# ProPrj_M-power_2025-07-25.net
KiCad netlist of a schematic drawn in EasyEDA Pro
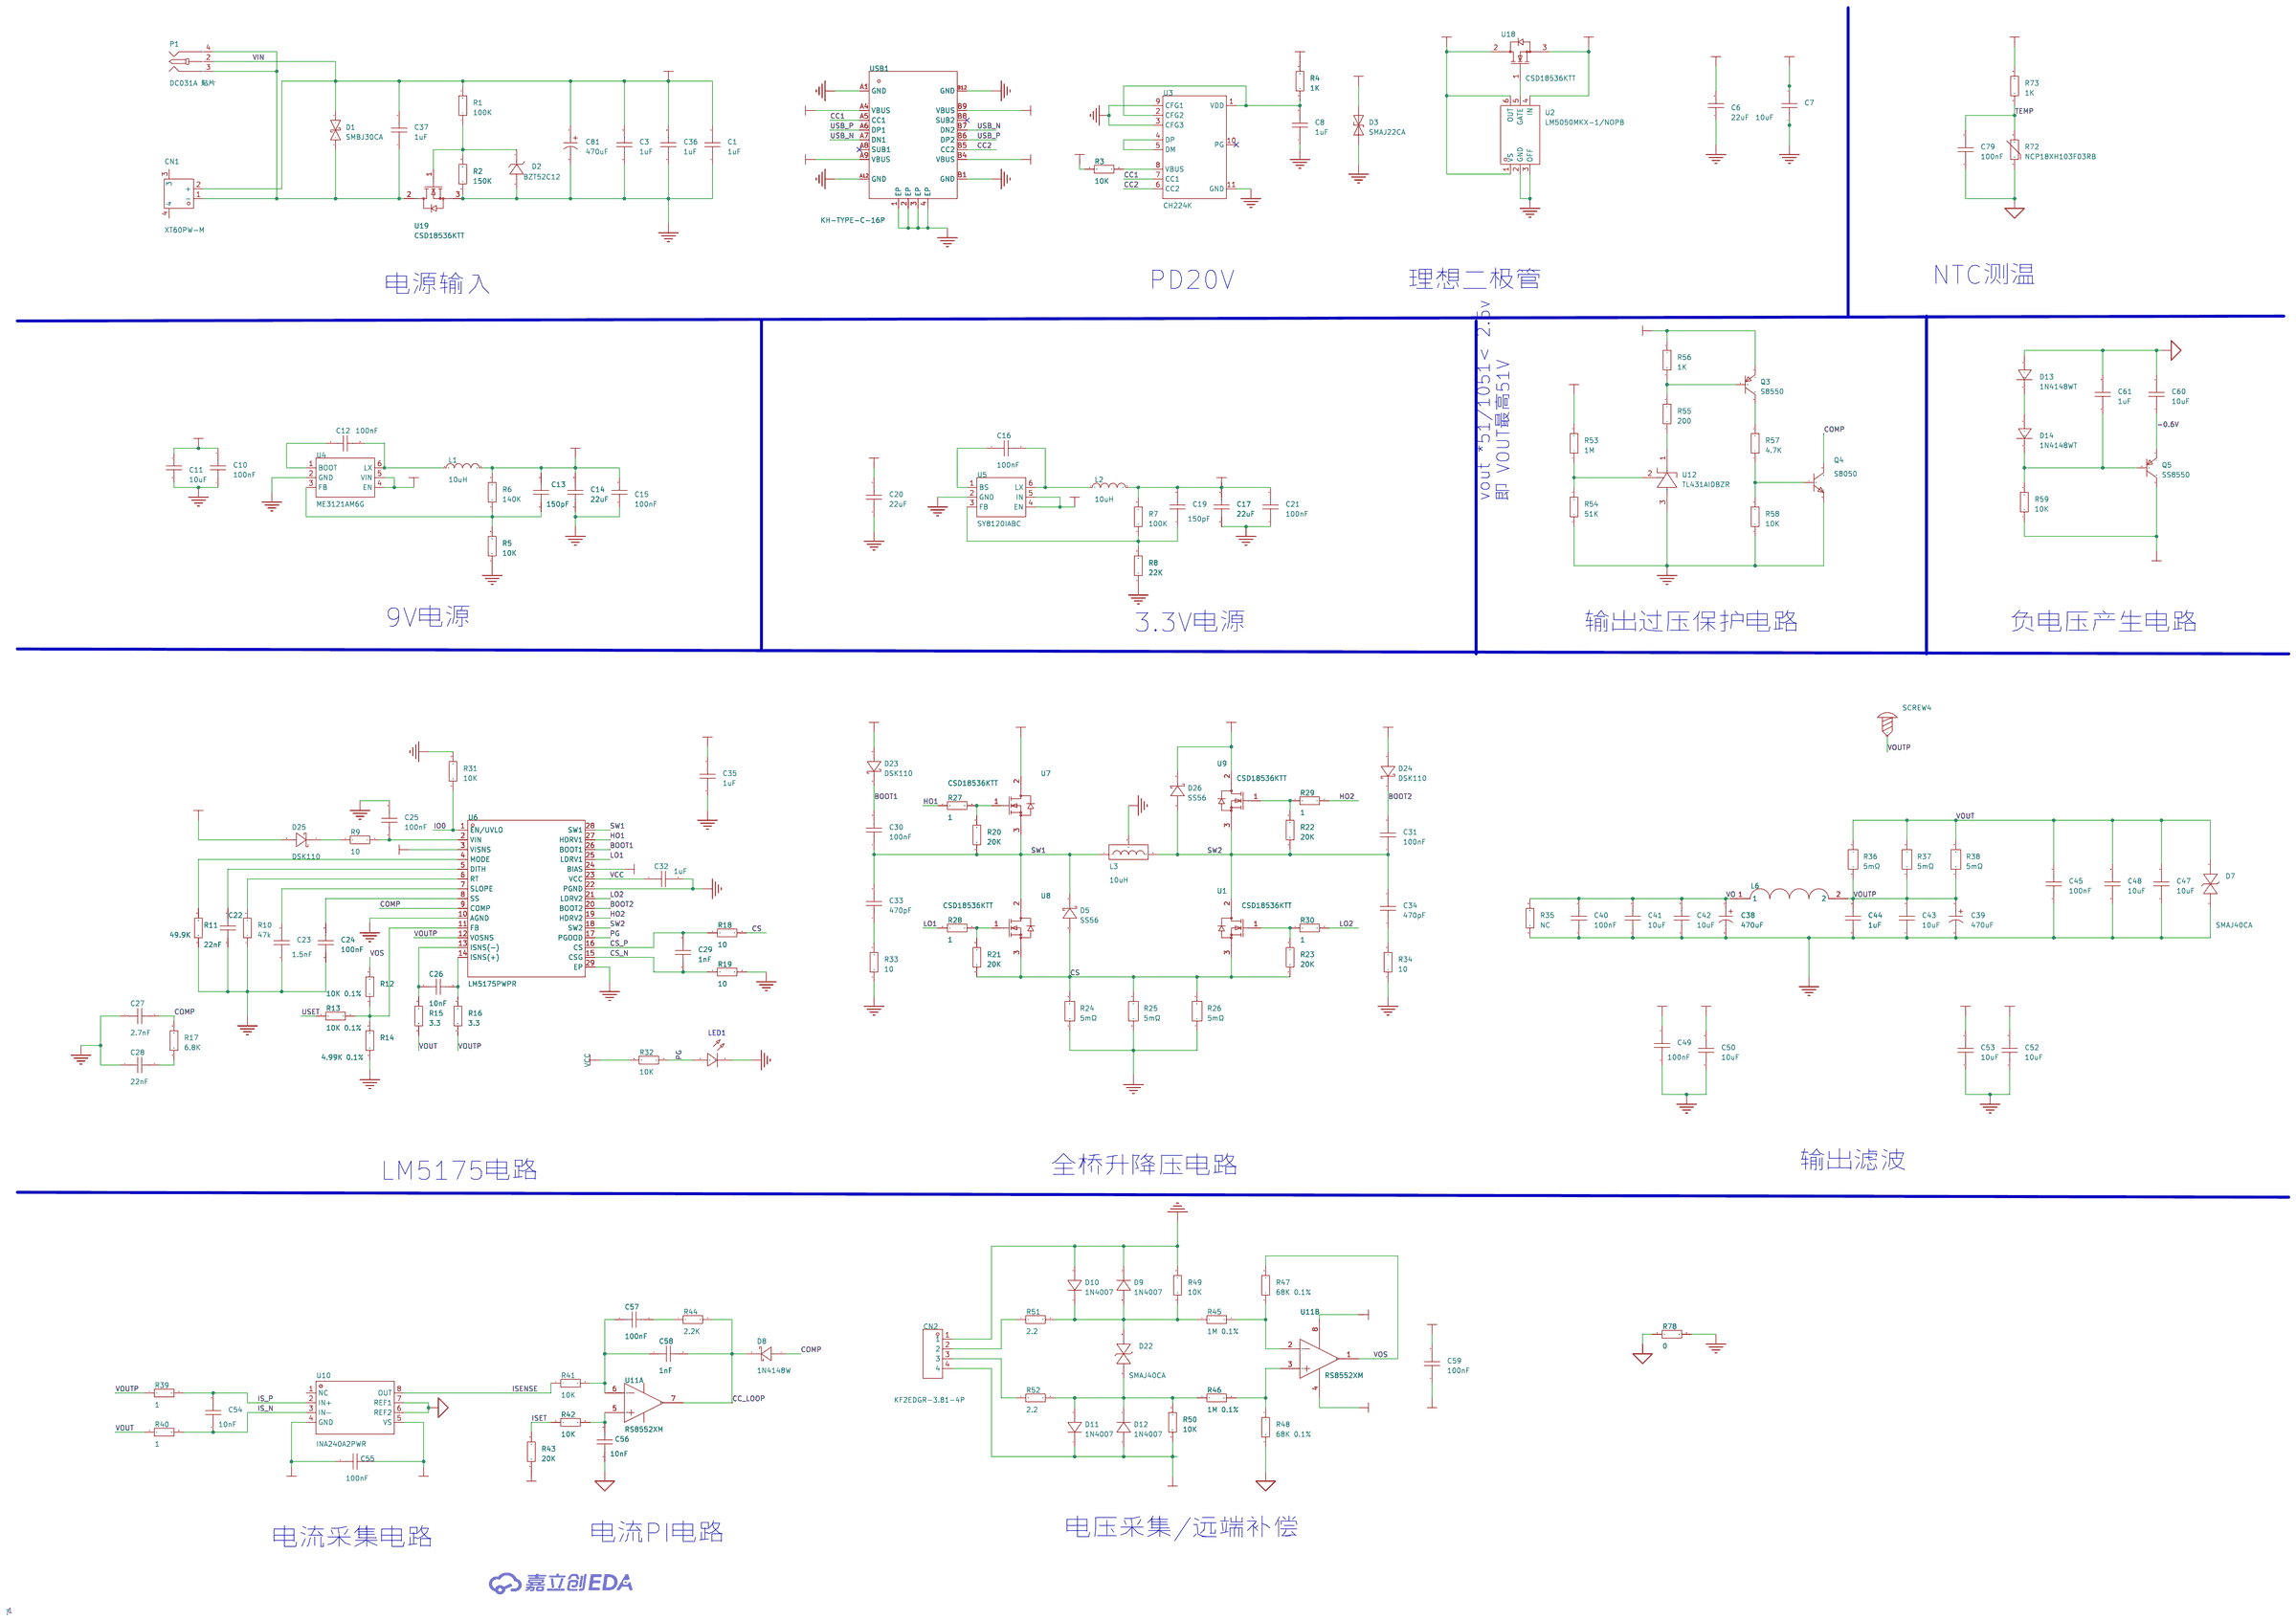
[diagram p0: 功率]
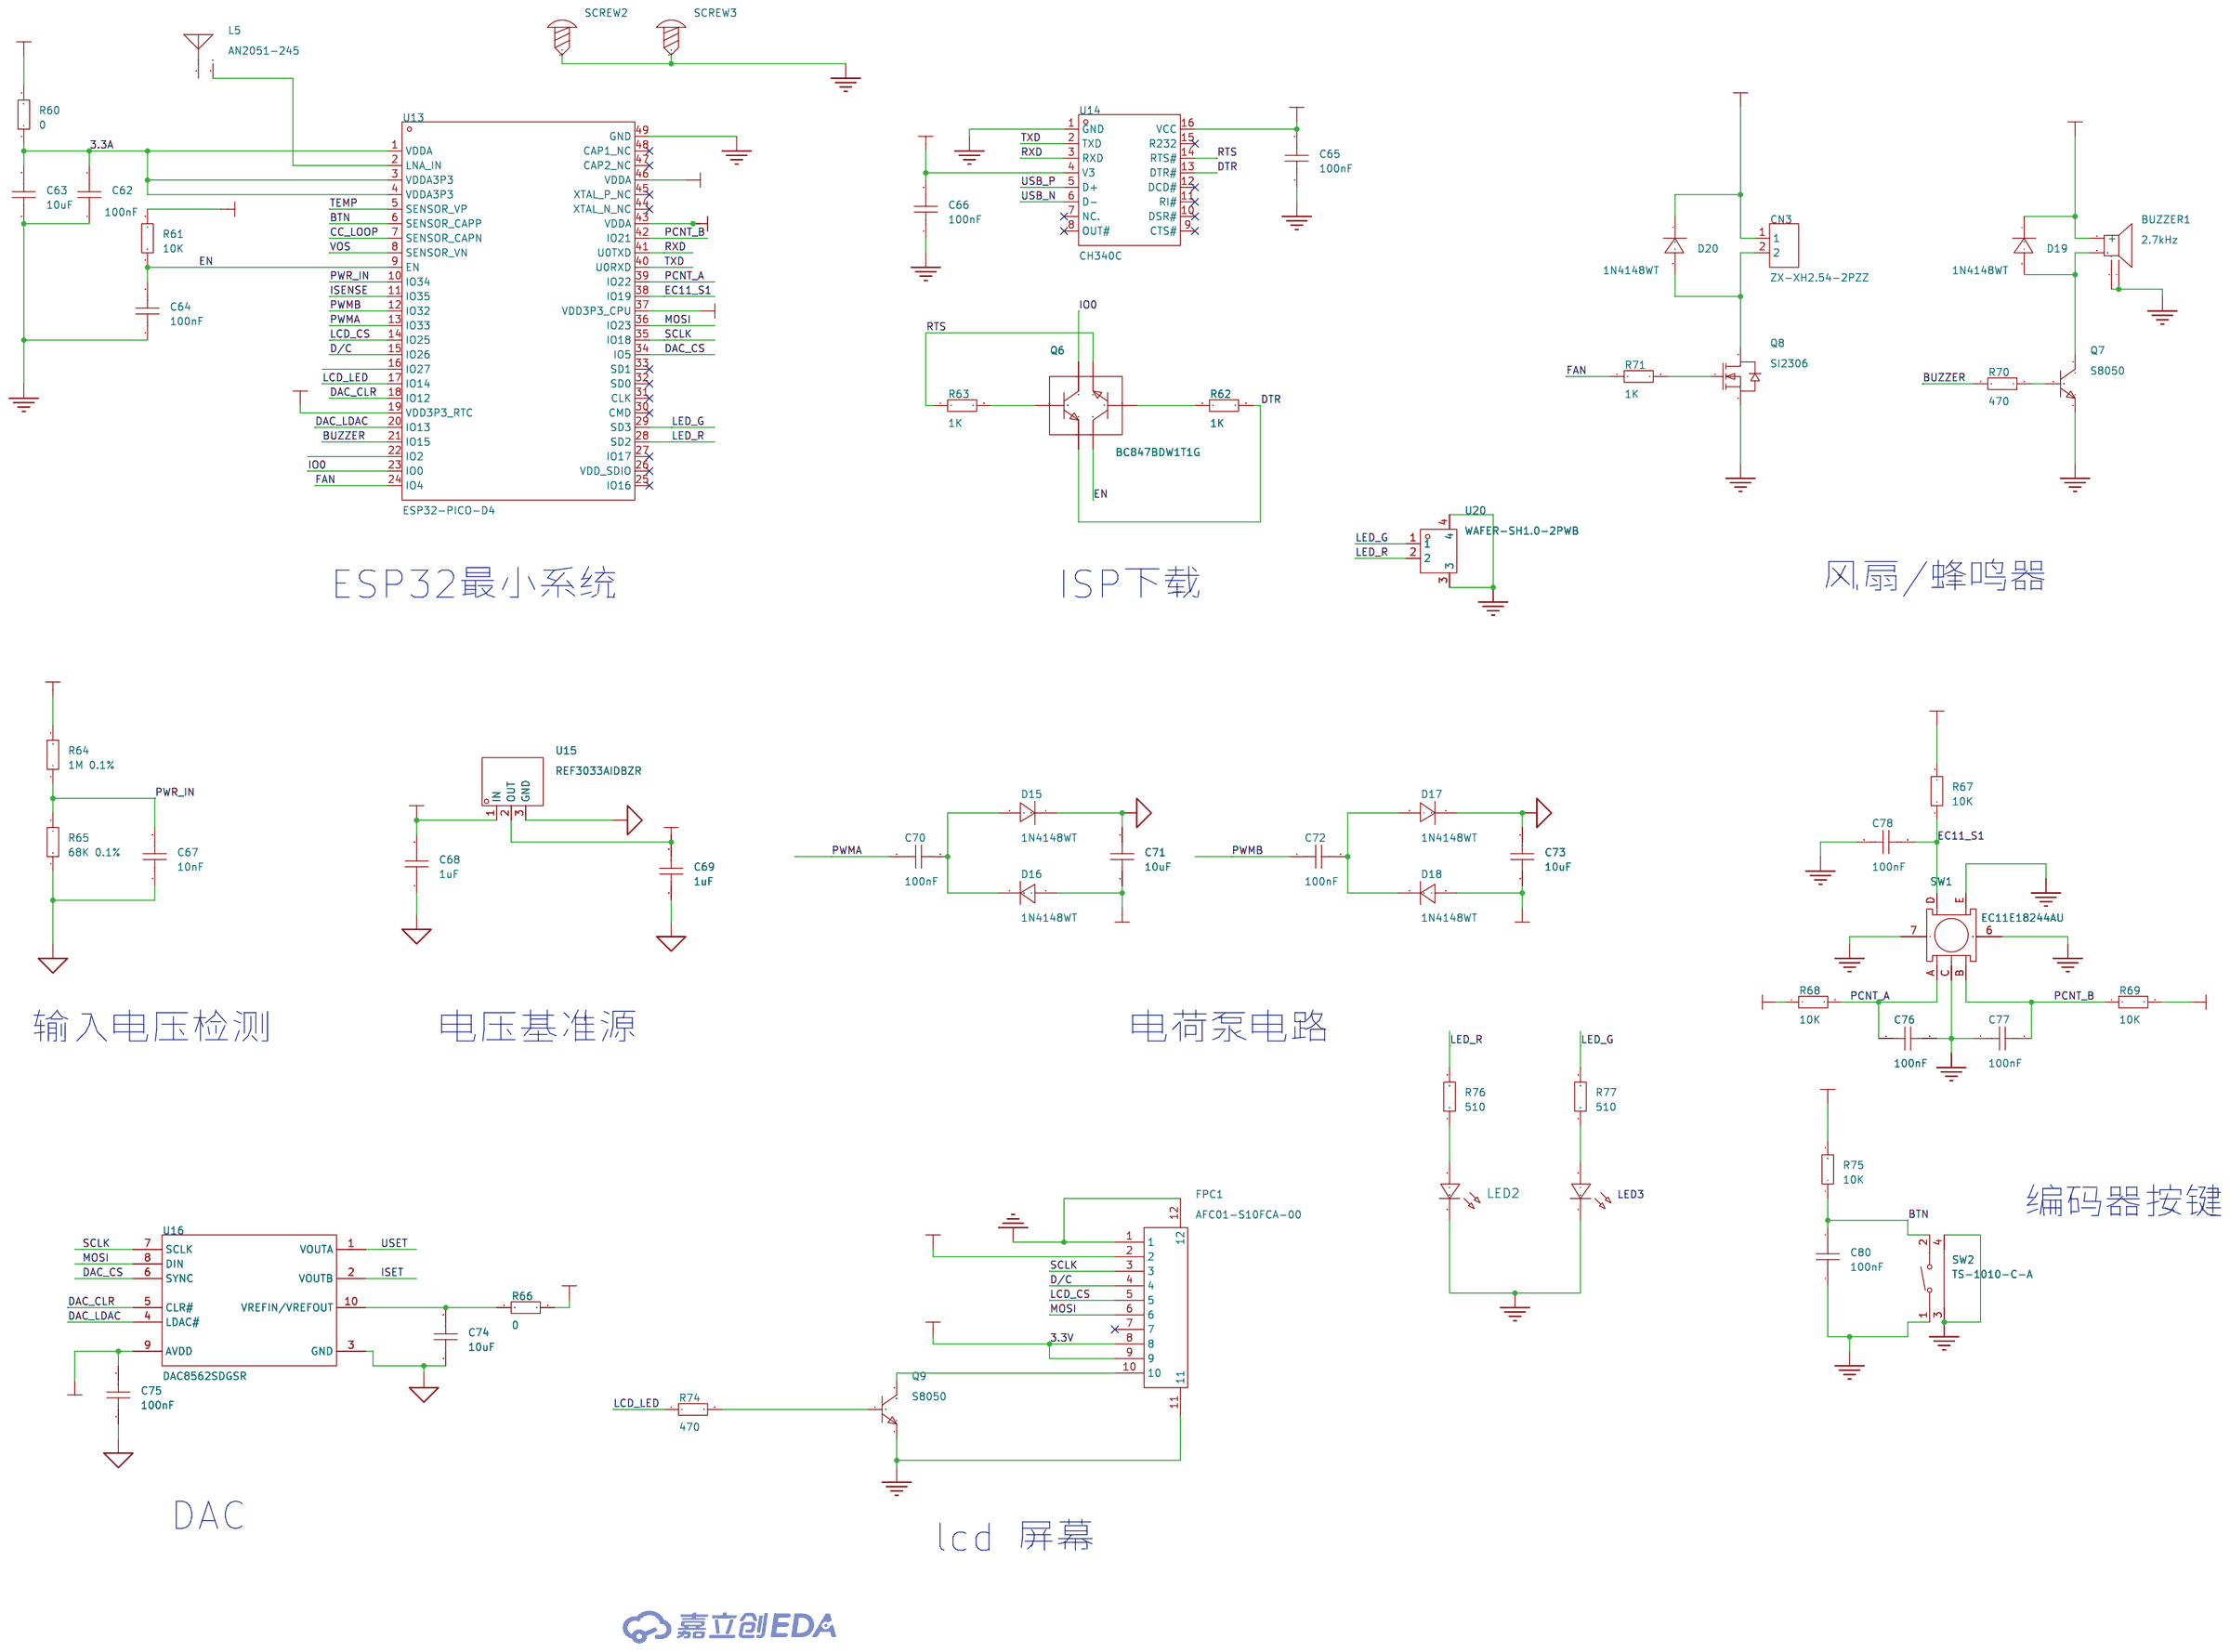
[diagram p1: 控制]

(export (version "E")
  (design (tool "Eeschema 10.0.6"))
  (components
    (comp (ref "C1")
      (value "1uF")
      (footprint "easyedapro:C0603")
      (fields
        (field (name "Manufacturer Part") "CL31B105KBHNNNE")
        (field (name "Manufacturer") "SAMSUNG(三星)")
      )
      (libsource (lib "easyedapro") (part "CapAcitance"))
    )
    (comp (ref "C3")
      (value "1uF")
      (footprint "easyedapro:C0603")
      (fields
        (field (name "Manufacturer Part") "CL31B105KBHNNNE")
        (field (name "Manufacturer") "SAMSUNG(三星)")
      )
      (libsource (lib "easyedapro") (part "CapAcitance"))
    )
    (comp (ref "C6")
      (value "22uF")
      (footprint "easyedapro:C1206")
      (description "容值:22uF;精度:±10%;额定电压:25V;材质(温度系数):X5R;")
      (fields
        (field (name "Manufacturer Part") "CL31A226KAHNNNE")
        (field (name "Manufacturer") "SAMSUNG(三星)")
      )
      (libsource (lib "easyedapro") (part "CL31A226KAHNNNE"))
    )
    (comp (ref "C7")
      (value "10uF")
      (footprint "easyedapro:C0603")
      (description "容值:10uF;精度:±20%;额定电压:25V;材质(温度系数):X5R;")
      (fields
        (field (name "Manufacturer Part") "CL10A106MA8NRNC")
        (field (name "Manufacturer") "SAMSUNG(三星)")
      )
      (libsource (lib "easyedapro") (part "CL10A106MA8NRNC"))
    )
    (comp (ref "C8")
      (value "1uF")
      (footprint "easyedapro:C0603")
      (libsource (lib "easyedapro") (part "CapAcitance"))
    )
    (comp (ref "C10")
      (value "100nF")
      (footprint "easyedapro:C0603")
      (libsource (lib "easyedapro") (part "CapAcitance"))
    )
    (comp (ref "C11")
      (value "10uF")
      (footprint "easyedapro:C1206")
      (description "容值:10uF;精度:±10%;额定电压:50V;材质(温度系数):X5R;")
      (fields
        (field (name "Manufacturer Part") "CL31A106KBHNNNE")
        (field (name "Manufacturer") "SAMSUNG(三星)")
      )
      (libsource (lib "easyedapro") (part "CL31A106KBHNNNE"))
    )
    (comp (ref "C12")
      (value "100nF")
      (footprint "easyedapro:C0603")
      (libsource (lib "easyedapro") (part "CapAcitance"))
    )
    (comp (ref "C13")
      (value "150pF")
      (footprint "easyedapro:C0603")
      (libsource (lib "easyedapro") (part "CapAcitance"))
    )
    (comp (ref "C14")
      (value "22uF")
      (footprint "easyedapro:C0805")
      (description "容值:22uF;精度:±20%;额定电压:25V;材质(温度系数):X5R;")
      (fields
        (field (name "Manufacturer Part") "CL21A226MAYNNNE")
        (field (name "Manufacturer") "SAMSUNG(三星)")
      )
      (libsource (lib "easyedapro") (part "CL21A226MAYNNNE"))
    )
    (comp (ref "C15")
      (value "100nF")
      (footprint "easyedapro:C1206")
      (description "容值:100uF;精度:±20%;额定电压:6.3V;材质(温度系数):X5R;")
      (fields
        (field (name "Manufacturer Part") "CL31A107MQHNNNE")
        (field (name "Manufacturer") "SAMSUNG(三星)")
      )
      (libsource (lib "easyedapro") (part "CL31A107MQHNNNE"))
    )
    (comp (ref "C16")
      (value "100nF")
      (footprint "easyedapro:C0603")
      (libsource (lib "easyedapro") (part "CapAcitance"))
    )
    (comp (ref "C17")
      (value "22uF")
      (footprint "easyedapro:C0603")
      (description "容值:22uF;精度:±20%;额定电压:6.3V;材质(温度系数):X5R;")
      (fields
        (field (name "Manufacturer Part") "CL10A226MQ8NRNC")
        (field (name "Manufacturer") "SAMSUNG(三星)")
      )
      (libsource (lib "easyedapro") (part "CL10A226MQ8NRNC"))
    )
    (comp (ref "C19")
      (value "150pF")
      (footprint "easyedapro:C0603")
      (libsource (lib "easyedapro") (part "CapAcitance"))
    )
    (comp (ref "C20")
      (value "22uF")
      (footprint "easyedapro:C0603")
      (description "容值:22uF;精度:±20%;额定电压:6.3V;材质(温度系数):X5R;")
      (fields
        (field (name "Manufacturer Part") "CL10A226MQ8NRNC")
        (field (name "Manufacturer") "SAMSUNG(三星)")
      )
      (libsource (lib "easyedapro") (part "CL10A226MQ8NRNC"))
    )
    (comp (ref "C21")
      (value "100nF")
      (footprint "easyedapro:C0603")
      (libsource (lib "easyedapro") (part "CapAcitance"))
    )
    (comp (ref "C22")
      (value "22nF")
      (footprint "easyedapro:C0603")
      (libsource (lib "easyedapro") (part "CapAcitance"))
    )
    (comp (ref "C23")
      (value "1.5nF")
      (footprint "easyedapro:C0603")
      (libsource (lib "easyedapro") (part "CapAcitance"))
    )
    (comp (ref "C24")
      (value "100nF")
      (footprint "easyedapro:C0603")
      (libsource (lib "easyedapro") (part "CapAcitance"))
    )
    (comp (ref "C25")
      (value "100nF")
      (footprint "easyedapro:C0603")
      (libsource (lib "easyedapro") (part "CapAcitance"))
    )
    (comp (ref "C26")
      (value "10nF")
      (footprint "easyedapro:C0603")
      (libsource (lib "easyedapro") (part "CapAcitance"))
    )
    (comp (ref "C27")
      (value "2.7nF")
      (footprint "easyedapro:C0603")
      (libsource (lib "easyedapro") (part "CapAcitance"))
    )
    (comp (ref "C28")
      (value "22nF")
      (footprint "easyedapro:C0603")
      (libsource (lib "easyedapro") (part "CapAcitance"))
    )
    (comp (ref "C29")
      (value "1nF")
      (footprint "easyedapro:C0603")
      (libsource (lib "easyedapro") (part "CapAcitance"))
    )
    (comp (ref "C30")
      (value "100nF")
      (footprint "easyedapro:C0603")
      (libsource (lib "easyedapro") (part "CapAcitance"))
    )
    (comp (ref "C31")
      (value "100nF")
      (footprint "easyedapro:C0603")
      (libsource (lib "easyedapro") (part "CapAcitance"))
    )
    (comp (ref "C32")
      (value "1uF")
      (footprint "easyedapro:C0603")
      (libsource (lib "easyedapro") (part "CapAcitance"))
    )
    (comp (ref "C33")
      (value "470pF")
      (footprint "easyedapro:C0603")
      (libsource (lib "easyedapro") (part "CapAcitance"))
    )
    (comp (ref "C34")
      (value "470pF")
      (footprint "easyedapro:C0603")
      (libsource (lib "easyedapro") (part "CapAcitance"))
    )
    (comp (ref "C35")
      (value "1uF")
      (footprint "easyedapro:C0603")
      (libsource (lib "easyedapro") (part "CapAcitance"))
    )
    (comp (ref "C36")
      (value "1uF")
      (footprint "easyedapro:C0603")
      (fields
        (field (name "Manufacturer Part") "CL31B105KBHNNNE")
        (field (name "Manufacturer") "SAMSUNG(三星)")
      )
      (libsource (lib "easyedapro") (part "CapAcitance"))
    )
    (comp (ref "C37")
      (value "1uF")
      (footprint "easyedapro:C0603")
      (fields
        (field (name "Manufacturer Part") "CL31B105KBHNNNE")
        (field (name "Manufacturer") "SAMSUNG(三星)")
      )
      (libsource (lib "easyedapro") (part "CapAcitance"))
    )
    (comp (ref "C38")
      (value "470uF")
      (footprint "easyedapro:CAP-TH_BD10.0-P5.00-D0.6-FD-A")
      (description "容值:470uF;精度:±20%;额定电压:50V;纹波电流:4.1A@100Hz;等效串联电阻(ESR):18mΩ@100kHz;类型:-;")
      (fields (field (name "Manufacturer Part") "PA50V470M10x17") (field (name "Manufacturer") "捷而瑞"))
      (libsource (lib "easyedapro") (part "PA50V470M10X17"))
    )
    (comp (ref "C39")
      (value "470uF")
      (footprint "easyedapro:CAP-TH_BD10.0-P5.00-D0.6-FD-A")
      (description "容值:470uF;精度:±20%;额定电压:50V;纹波电流:4.1A@100Hz;等效串联电阻(ESR):18mΩ@100kHz;类型:-;")
      (fields (field (name "Manufacturer Part") "PA50V470M10x17") (field (name "Manufacturer") "捷而瑞"))
      (libsource (lib "easyedapro") (part "PA50V470M10X17"))
    )
    (comp (ref "C40")
      (value "100nF")
      (footprint "easyedapro:C0603")
      (libsource (lib "easyedapro") (part "CapAcitance"))
    )
    (comp (ref "C41")
      (value "10uF")
      (footprint "easyedapro:C0603")
      (fields
        (field (name "Manufacturer Part") "CL31B105KBHNNNE")
        (field (name "Manufacturer") "SAMSUNG(三星)")
      )
      (libsource (lib "easyedapro") (part "CapAcitance"))
    )
    (comp (ref "C42")
      (value "10uF")
      (footprint "easyedapro:C0603")
      (fields
        (field (name "Manufacturer Part") "CL31B105KBHNNNE")
        (field (name "Manufacturer") "SAMSUNG(三星)")
      )
      (libsource (lib "easyedapro") (part "CapAcitance"))
    )
    (comp (ref "C43")
      (value "10uF")
      (footprint "easyedapro:C0603")
      (fields
        (field (name "Manufacturer Part") "CL31B105KBHNNNE")
        (field (name "Manufacturer") "SAMSUNG(三星)")
      )
      (libsource (lib "easyedapro") (part "CapAcitance"))
    )
    (comp (ref "C44")
      (value "1uF")
      (footprint "easyedapro:C0603")
      (fields
        (field (name "Manufacturer Part") "CL31B105KBHNNNE")
        (field (name "Manufacturer") "SAMSUNG(三星)")
      )
      (libsource (lib "easyedapro") (part "CapAcitance"))
    )
    (comp (ref "C45")
      (value "100nF")
      (footprint "easyedapro:C0603")
      (libsource (lib "easyedapro") (part "CapAcitance"))
    )
    (comp (ref "C47")
      (value "10uF")
      (footprint "easyedapro:C0603")
      (fields
        (field (name "Manufacturer Part") "CL31B105KBHNNNE")
        (field (name "Manufacturer") "SAMSUNG(三星)")
      )
      (libsource (lib "easyedapro") (part "CapAcitance"))
    )
    (comp (ref "C48")
      (value "10uF")
      (footprint "easyedapro:C0603")
      (fields
        (field (name "Manufacturer Part") "CL31B105KBHNNNE")
        (field (name "Manufacturer") "SAMSUNG(三星)")
      )
      (libsource (lib "easyedapro") (part "CapAcitance"))
    )
    (comp (ref "C49")
      (value "100nF")
      (footprint "easyedapro:C0603")
      (libsource (lib "easyedapro") (part "CapAcitance"))
    )
    (comp (ref "C50")
      (value "10uF")
      (footprint "easyedapro:C0603")
      (fields
        (field (name "Manufacturer Part") "CL31B105KBHNNNE")
        (field (name "Manufacturer") "SAMSUNG(三星)")
      )
      (libsource (lib "easyedapro") (part "CapAcitance"))
    )
    (comp (ref "C52")
      (value "10uF")
      (footprint "easyedapro:C0603")
      (fields
        (field (name "Manufacturer Part") "CL31B105KBHNNNE")
        (field (name "Manufacturer") "SAMSUNG(三星)")
      )
      (libsource (lib "easyedapro") (part "CapAcitance"))
    )
    (comp (ref "C53")
      (value "10uF")
      (footprint "easyedapro:C0603")
      (fields
        (field (name "Manufacturer Part") "CL31B105KBHNNNE")
        (field (name "Manufacturer") "SAMSUNG(三星)")
      )
      (libsource (lib "easyedapro") (part "CapAcitance"))
    )
    (comp (ref "C54")
      (value "10nF")
      (footprint "easyedapro:C0603")
      (libsource (lib "easyedapro") (part "CapAcitance"))
    )
    (comp (ref "C55")
      (value "100nF")
      (footprint "easyedapro:C0603")
      (libsource (lib "easyedapro") (part "CapAcitance"))
    )
    (comp (ref "C56")
      (value "10nF")
      (footprint "easyedapro:C0603")
      (libsource (lib "easyedapro") (part "CapAcitance"))
    )
    (comp (ref "C57")
      (value "100nF")
      (footprint "easyedapro:C0603")
      (libsource (lib "easyedapro") (part "CapAcitance"))
    )
    (comp (ref "C58")
      (value "1nF")
      (footprint "easyedapro:C0603")
      (libsource (lib "easyedapro") (part "CapAcitance"))
    )
    (comp (ref "C59")
      (value "100nF")
      (footprint "easyedapro:C0603")
      (libsource (lib "easyedapro") (part "CapAcitance"))
    )
    (comp (ref "C60")
      (value "10uF")
      (footprint "easyedapro:C0603")
      (libsource (lib "easyedapro") (part "CapAcitance"))
    )
    (comp (ref "C61")
      (value "1uF")
      (footprint "easyedapro:C0603")
      (libsource (lib "easyedapro") (part "CapAcitance"))
    )
    (comp (ref "C79")
      (value "100nF")
      (footprint "easyedapro:C0603")
      (libsource (lib "easyedapro") (part "CapAcitance"))
    )
    (comp (ref "C81")
      (value "470uF")
      (footprint "easyedapro:CAP-TH_BD10.0-P5.00-D0.6-FD-A")
      (description "容值:470uF;精度:±20%;额定电压:50V;纹波电流:4.1A@100Hz;等效串联电阻(ESR):18mΩ@100kHz;类型:-;")
      (fields (field (name "Manufacturer Part") "PA50V470M10x17") (field (name "Manufacturer") "捷而瑞"))
      (libsource (lib "easyedapro") (part "PA50V470M10X17"))
    )
    (comp (ref "CN1")
      (value "XT60PW-M")
      (footprint "easyedapro:CONN-TH_XT60PW-M")
      (description "类别:-;类型1:-;")
      (fields (field (name "Manufacturer") "AMASS(艾迈斯)"))
      (libsource (lib "easyedapro") (part "XT60PW-M"))
    )
    (comp (ref "CN2")
      (value "KF2EDGR-3.81-4P")
      (footprint "easyedapro:CONN-TH_4P-P3.81_KF2EDGR-3.81-4P")
      (fields (field (name "Manufacturer") "KEFA(科发)"))
      (libsource (lib "easyedapro") (part "KF2EDGR-3.81-4P"))
    )
    (comp (ref "D1")
      (value "SMBJ30CA")
      (footprint "easyedapro:SMB_L4.6-W3.6-LS5.3-BI")
      (description "反向截止电压(Vrwm):30V;最大钳位电压:48.4V;峰值脉冲电流(Ipp)@10/1000us:12.4A;击穿电压:33.3V;")
      (fields (field (name "Manufacturer") "MDD"))
      (libsource (lib "easyedapro") (part "SMBJ30CA_C113999"))
    )
    (comp (ref "D2")
      (value "BZT52C12")
      (footprint "easyedapro:SOD-123_L2.7-W1.6-LS3.7-RD")
      (description "二极管配置:独立式;稳压值(标称值):12V;稳压值(范围):11.4V~12.6V;功率(Pd):500mW;")
      (fields (field (name "Manufacturer") "宏迦橙"))
      (libsource (lib "easyedapro") (part "BZT52C12_C19077410"))
    )
    (comp (ref "D3")
      (value "SMAJ22CA")
      (footprint "easyedapro:SMA_L4.4-W2.6-LS5.0-BI")
      (description "反向截止电压(Vrwm):22V;最大钳位电压:35.5V;峰值脉冲电流(Ipp):11.3A;峰值脉冲功率(Ppp):400W;击穿电压:24.4V;")
      (fields (field (name "Manufacturer") "Littelfuse(美国力特)"))
      (libsource (lib "easyedapro") (part "SMAJ22CA"))
    )
    (comp (ref "D5")
      (value "SS56")
      (footprint "easyedapro:SMA_L4.3-W2.6-LS5.0-RD")
      (description "二极管配置:独立式;正向压降(Vf):700mV@5.0A;直流反向耐压(Vr):60V;整流电流:5A;")
      (fields (field (name "Manufacturer") "宏迦橙"))
      (libsource (lib "easyedapro") (part "SS56_C18199169"))
    )
    (comp (ref "D7")
      (value "SMAJ40CA")
      (footprint "easyedapro:SMA_L4.3-W2.6-LS5.0-BI")
      (description "极性:双向;反向截止电压(Vrwm):40V;钳位电压:64.5V;峰值脉冲电流(Ipp):6.2A;峰值脉冲功率(Ppp):400W;击穿电压:44.4V;")
      (fields (field (name "Manufacturer") "宏嘉诚"))
      (libsource (lib "easyedapro") (part "SMAJ40CA_C19077552"))
    )
    (comp (ref "D8")
      (value "1N4148W")
      (footprint "easyedapro:SOD-123_L2.7-W1.6-LS3.7-FD")
      (description "二极管配置:独立式;正向压降(Vf):1.25V@150mA;直流反向耐压(Vr):100V;整流电流:150mA;反向恢复时间(trr):4ns;")
      (fields (field (name "Manufacturer") "宏迦橙"))
      (libsource (lib "easyedapro") (part "1N4148W_C7420318"))
    )
    (comp (ref "D9")
      (value "1N4007")
      (footprint "easyedapro:SMA_L4.3-W2.5-LS5.0-RD")
      (description "二极管配置:独立式;正向压降(Vf):1.1V@1A;直流反向耐压(Vr):1kV;整流电流:1A;")
      (fields (field (name "Manufacturer") "TWGMC(台湾迪嘉)"))
      (libsource (lib "easyedapro") (part "1N4007_C727081"))
    )
    (comp (ref "D10")
      (value "1N4007")
      (footprint "easyedapro:SMA_L4.3-W2.5-LS5.0-RD")
      (description "二极管配置:独立式;正向压降(Vf):1.1V@1A;直流反向耐压(Vr):1kV;整流电流:1A;")
      (fields (field (name "Manufacturer") "TWGMC(台湾迪嘉)"))
      (libsource (lib "easyedapro") (part "1N4007_C727081"))
    )
    (comp (ref "D11")
      (value "1N4007")
      (footprint "easyedapro:SMA_L4.3-W2.5-LS5.0-RD")
      (description "二极管配置:独立式;正向压降(Vf):1.1V@1A;直流反向耐压(Vr):1kV;整流电流:1A;")
      (fields (field (name "Manufacturer") "TWGMC(台湾迪嘉)"))
      (libsource (lib "easyedapro") (part "1N4007_C727081"))
    )
    (comp (ref "D12")
      (value "1N4007")
      (footprint "easyedapro:SMA_L4.3-W2.5-LS5.0-RD")
      (description "二极管配置:独立式;正向压降(Vf):1.1V@1A;直流反向耐压(Vr):1kV;整流电流:1A;")
      (fields (field (name "Manufacturer") "TWGMC(台湾迪嘉)"))
      (libsource (lib "easyedapro") (part "1N4007_C727081"))
    )
    (comp (ref "D13")
      (value "1N4148WT")
      (footprint "easyedapro:SOD-523_L1.2-W0.8-LS1.6-RD")
      (description "二极管配置:独立式;正向压降(Vf):1V@10mA;直流反向耐压(Vr):75V;整流电流:300mA;反向恢复时间(trr):4ns;")
      (fields (field (name "Manufacturer") "onsemi(安森美)"))
      (libsource (lib "easyedapro") (part "1N4148WT_C232841"))
    )
    (comp (ref "D14")
      (value "1N4148WT")
      (footprint "easyedapro:SOD-523_L1.2-W0.8-LS1.6-RD")
      (description "二极管配置:独立式;正向压降(Vf):1V@10mA;直流反向耐压(Vr):75V;整流电流:300mA;反向恢复时间(trr):4ns;")
      (fields (field (name "Manufacturer") "onsemi(安森美)"))
      (libsource (lib "easyedapro") (part "1N4148WT_C232841"))
    )
    (comp (ref "D22")
      (value "SMAJ40CA")
      (footprint "easyedapro:SMA_L4.3-W2.6-LS5.0-BI")
      (description "极性:双向;反向截止电压(Vrwm):40V;钳位电压:64.5V;峰值脉冲电流(Ipp):6.2A;峰值脉冲功率(Ppp):400W;击穿电压:44.4V;")
      (fields (field (name "Manufacturer") "宏嘉诚"))
      (libsource (lib "easyedapro") (part "SMAJ40CA_C19077552"))
    )
    (comp (ref "D23")
      (value "DSK110")
      (footprint "easyedapro:SOD-123FL_L2.8-W1.9-LS3.7-RD")
      (description "二极管配置:独立式;正向压降(Vf):850mV@1A;直流反向耐压(Vr):100V;整流电流:1A;")
      (fields (field (name "Manufacturer") "宏迦橙"))
      (libsource (lib "easyedapro") (part "DSK110_C22466354"))
    )
    (comp (ref "D24")
      (value "DSK110")
      (footprint "easyedapro:SOD-123FL_L2.8-W1.9-LS3.7-RD")
      (description "二极管配置:独立式;正向压降(Vf):850mV@1A;直流反向耐压(Vr):100V;整流电流:1A;")
      (fields (field (name "Manufacturer") "宏迦橙"))
      (libsource (lib "easyedapro") (part "DSK110_C22466354"))
    )
    (comp (ref "D25")
      (value "DSK110")
      (footprint "easyedapro:SOD-123FL_L2.8-W1.9-LS3.7-RD")
      (description "二极管配置:独立式;正向压降(Vf):850mV@1A;直流反向耐压(Vr):100V;整流电流:1A;")
      (fields (field (name "Manufacturer") "宏迦橙"))
      (libsource (lib "easyedapro") (part "DSK110_C22466354"))
    )
    (comp (ref "D26")
      (value "SS56")
      (footprint "easyedapro:SMA_L4.3-W2.6-LS5.0-RD")
      (description "二极管配置:独立式;正向压降(Vf):700mV@5.0A;直流反向耐压(Vr):60V;整流电流:5A;")
      (fields (field (name "Manufacturer") "宏迦橙"))
      (libsource (lib "easyedapro") (part "SS56_C18199169"))
    )
    (comp (ref "L1")
      (value "10uH")
      (footprint "easyedapro:IND-SMD_L7.0-W6.6_FXL0630")
      (description "电感值:33uH;精度:±20%;额定电流:2A;饱和电流(Isat):2.5A;类型:一体成型电感;")
      (fields (field (name "Manufacturer Part") "FXL0630-330-M") (field (name "Manufacturer") "cjiang(长江微电)"))
      (libsource (lib "easyedapro") (part "FXL0630-330-M"))
    )
    (comp (ref "L2")
      (value "10uH")
      (footprint "easyedapro:IND-SMD_L7.3-W6.8")
      (description "电感值:10uH;精度:±20%;额定电流:4.5A;饱和电流(Isat):5.5A;类型:一体成型电感;")
      (fields (field (name "Manufacturer Part") "FXL0630-100-M") (field (name "Manufacturer") "cjiang(长江微电)"))
      (libsource (lib "easyedapro") (part "FXL0630-100-M"))
    )
    (comp (ref "L3")
      (value "10uH")
      (footprint "easyedapro:IND-SMD_3P-L28.0-W19.4_7443641000B")
      (description "电感值:10uH;精度:±20%;额定电流:30A;饱和电流(Isat):31A;类型:扁平线大电流电感;")
      (fields (field (name "Manufacturer Part") "MTP2918S-100M") (field (name "Manufacturer") "COILMX(迈翔科技)"))
      (libsource (lib "easyedapro") (part "MTP2918S-100M"))
    )
    (comp (ref "L6") (value "~") (libsource (lib "easyedapro") (part "磁棒电感1.5uh")))
    (comp (ref "LED1")
      (value "~")
      (footprint "easyedapro:LED_0603")
      (libsource (lib "easyedapro") (part "LED_G"))
    )
    (comp (ref "P1")
      (value "DC031A 贴片")
      (footprint "easyedapro:DC-IN-SMD_DC031A")
      (description "连接器类型:DC电源插座;安装方式:卧贴;触点内径:1.3mm;触点外径:3.7mm;额定电流:-;额定电压:-;工作温度范围:-;")
      (fields (field (name "Manufacturer") "BOOMELE(博穆精密)"))
      (libsource (lib "easyedapro") (part "DC031A DCseat"))
    )
    (comp (ref "Q3")
      (value "S8550")
      (footprint "easyedapro:SOT-23-3_L2.9-W1.3-P1.90-LS2.4-BR")
      (description "晶体管类型:PNP;集电极电流(Ic):500mA;集射极击穿电压(Vceo):25V;耗散功率(Pd):300mW;直流电流增益(hFE):120@500mA,1.0V;")
      (fields (field (name "Manufacturer") "宏嘉诚"))
      (libsource (lib "easyedapro") (part "S8550_C20069126"))
    )
    (comp (ref "Q4")
      (value "S8050")
      (footprint "easyedapro:SOT-23-3_L2.9-W1.3-P1.90-LS2.3-BR")
      (description "晶体管类型:NPN;集电极电流(Ic):500mA;集射极击穿电压(Vceo):25V;耗散功率(Pd):300mW;直流电流增益(hFE):120@50mA,1.0V;")
      (fields (field (name "Manufacturer") "宏嘉诚"))
      (libsource (lib "easyedapro") (part "S8050_C20069125"))
    )
    (comp (ref "Q5")
      (value "SS8550")
      (footprint "easyedapro:SOT-23-3_L2.9-W1.3-P1.90-LS2.4-BR")
      (description "晶体管类型:PNP;集电极电流(Ic):1.5A;集射极击穿电压(Vceo):25V;耗散功率(Pd):300mW;直流电流增益(hFE):120@100mA,1.0V;")
      (fields (field (name "Manufacturer") "宏嘉诚"))
      (libsource (lib "easyedapro") (part "SS8550_C7420371"))
    )
    (comp (ref "R1") (value "100K") (footprint "easyedapro:R0603") (libsource (lib "easyedapro") (part "电阻")))
    (comp (ref "R2") (value "150K") (footprint "easyedapro:R0603") (libsource (lib "easyedapro") (part "电阻")))
    (comp (ref "R3") (value "10K") (footprint "easyedapro:R0603") (libsource (lib "easyedapro") (part "电阻")))
    (comp (ref "R4") (value "1K") (footprint "easyedapro:R0603") (libsource (lib "easyedapro") (part "电阻")))
    (comp (ref "R5") (value "10K") (footprint "easyedapro:R0603") (libsource (lib "easyedapro") (part "电阻")))
    (comp (ref "R6") (value "140K") (footprint "easyedapro:R0603") (libsource (lib "easyedapro") (part "电阻")))
    (comp (ref "R7") (value "100K") (footprint "easyedapro:R0603") (libsource (lib "easyedapro") (part "电阻")))
    (comp (ref "R8") (value "22K") (footprint "easyedapro:R0603") (libsource (lib "easyedapro") (part "电阻")))
    (comp (ref "R9") (value "10") (footprint "easyedapro:R0603") (libsource (lib "easyedapro") (part "电阻")))
    (comp (ref "R10") (value "47k") (footprint "easyedapro:R0603") (libsource (lib "easyedapro") (part "电阻")))
    (comp (ref "R11")
      (value "49.9K")
      (footprint "easyedapro:R0603")
      (libsource (lib "easyedapro") (part "电阻"))
    )
    (comp (ref "R12")
      (value "10K 0.1%")
      (footprint "easyedapro:R0603")
      (libsource (lib "easyedapro") (part "电阻"))
    )
    (comp (ref "R13")
      (value "10K 0.1%")
      (footprint "easyedapro:R0603")
      (libsource (lib "easyedapro") (part "电阻"))
    )
    (comp (ref "R14")
      (value "4.99K 0.1%")
      (footprint "easyedapro:R0603")
      (libsource (lib "easyedapro") (part "电阻"))
    )
    (comp (ref "R15") (value "3.3") (footprint "easyedapro:R0603") (libsource (lib "easyedapro") (part "电阻")))
    (comp (ref "R16") (value "3.3") (footprint "easyedapro:R0603") (libsource (lib "easyedapro") (part "电阻")))
    (comp (ref "R17")
      (value "6.8K")
      (footprint "easyedapro:R0603")
      (libsource (lib "easyedapro") (part "电阻"))
    )
    (comp (ref "R18") (value "10") (footprint "easyedapro:R0603") (libsource (lib "easyedapro") (part "电阻")))
    (comp (ref "R19") (value "10") (footprint "easyedapro:R0603") (libsource (lib "easyedapro") (part "电阻")))
    (comp (ref "R20") (value "20K") (footprint "easyedapro:R0603") (libsource (lib "easyedapro") (part "电阻")))
    (comp (ref "R21") (value "20K") (footprint "easyedapro:R0603") (libsource (lib "easyedapro") (part "电阻")))
    (comp (ref "R22") (value "20K") (footprint "easyedapro:R0603") (libsource (lib "easyedapro") (part "电阻")))
    (comp (ref "R23") (value "20K") (footprint "easyedapro:R0603") (libsource (lib "easyedapro") (part "电阻")))
    (comp (ref "R24")
      (value "5mΩ")
      (footprint "easyedapro:R2512")
      (description "电阻类型:采样电阻;阻值:5mΩ;精度:±1%;功率:3W;温度系数:±50ppm/°C;")
      (fields (field (name "Manufacturer Part") "JER2512F3R005") (field (name "Manufacturer") "捷而瑞"))
      (libsource (lib "easyedapro") (part "JER2512F3R005"))
    )
    (comp (ref "R25")
      (value "5mΩ")
      (footprint "easyedapro:R2512")
      (description "电阻类型:采样电阻;阻值:5mΩ;精度:±1%;功率:3W;温度系数:±50ppm/°C;")
      (fields (field (name "Manufacturer Part") "JER2512F3R005") (field (name "Manufacturer") "捷而瑞"))
      (libsource (lib "easyedapro") (part "JER2512F3R005"))
    )
    (comp (ref "R26")
      (value "5mΩ")
      (footprint "easyedapro:R2512")
      (description "电阻类型:采样电阻;阻值:5mΩ;精度:±1%;功率:3W;温度系数:±50ppm/°C;")
      (fields (field (name "Manufacturer Part") "JER2512F3R005") (field (name "Manufacturer") "捷而瑞"))
      (libsource (lib "easyedapro") (part "JER2512F3R005"))
    )
    (comp (ref "R27") (value "1") (footprint "easyedapro:R0603") (libsource (lib "easyedapro") (part "电阻")))
    (comp (ref "R28") (value "1") (footprint "easyedapro:R0603") (libsource (lib "easyedapro") (part "电阻")))
    (comp (ref "R29") (value "1") (footprint "easyedapro:R0603") (libsource (lib "easyedapro") (part "电阻")))
    (comp (ref "R30") (value "1") (footprint "easyedapro:R0603") (libsource (lib "easyedapro") (part "电阻")))
    (comp (ref "R31") (value "10K") (footprint "easyedapro:R0603") (libsource (lib "easyedapro") (part "电阻")))
    (comp (ref "R32") (value "10K") (footprint "easyedapro:R0603") (libsource (lib "easyedapro") (part "电阻")))
    (comp (ref "R33") (value "10") (footprint "easyedapro:R0603") (libsource (lib "easyedapro") (part "电阻")))
    (comp (ref "R34") (value "10") (footprint "easyedapro:R0603") (libsource (lib "easyedapro") (part "电阻")))
    (comp (ref "R35") (value "NC") (footprint "easyedapro:R0603") (libsource (lib "easyedapro") (part "电阻")))
    (comp (ref "R36")
      (value "5mΩ")
      (footprint "easyedapro:R2512")
      (description "电阻类型:采样电阻;阻值:5mΩ;精度:±1%;功率:3W;温度系数:±50ppm/°C;")
      (fields (field (name "Manufacturer Part") "JER2512F3R005") (field (name "Manufacturer") "捷而瑞"))
      (libsource (lib "easyedapro") (part "JER2512F3R005"))
    )
    (comp (ref "R37")
      (value "5mΩ")
      (footprint "easyedapro:R2512")
      (description "电阻类型:采样电阻;阻值:5mΩ;精度:±1%;功率:3W;温度系数:±50ppm/°C;")
      (fields (field (name "Manufacturer Part") "JER2512F3R005") (field (name "Manufacturer") "捷而瑞"))
      (libsource (lib "easyedapro") (part "JER2512F3R005"))
    )
    (comp (ref "R38")
      (value "5mΩ")
      (footprint "easyedapro:R2512")
      (description "电阻类型:采样电阻;阻值:5mΩ;精度:±1%;功率:3W;温度系数:±50ppm/°C;")
      (fields (field (name "Manufacturer Part") "JER2512F3R005") (field (name "Manufacturer") "捷而瑞"))
      (libsource (lib "easyedapro") (part "JER2512F3R005"))
    )
    (comp (ref "R39") (value "1") (footprint "easyedapro:R0603") (libsource (lib "easyedapro") (part "电阻")))
    (comp (ref "R40") (value "1") (footprint "easyedapro:R0603") (libsource (lib "easyedapro") (part "电阻")))
    (comp (ref "R41") (value "10K") (footprint "easyedapro:R0603") (libsource (lib "easyedapro") (part "电阻")))
    (comp (ref "R42") (value "10K") (footprint "easyedapro:R0603") (libsource (lib "easyedapro") (part "电阻")))
    (comp (ref "R43") (value "20K") (footprint "easyedapro:R0603") (libsource (lib "easyedapro") (part "电阻")))
    (comp (ref "R44")
      (value "2.2K")
      (footprint "easyedapro:R0603")
      (libsource (lib "easyedapro") (part "电阻"))
    )
    (comp (ref "R45")
      (value "1M 0.1%")
      (footprint "easyedapro:R0603")
      (libsource (lib "easyedapro") (part "电阻"))
    )
    (comp (ref "R46")
      (value "1M 0.1%")
      (footprint "easyedapro:R0603")
      (libsource (lib "easyedapro") (part "电阻"))
    )
    (comp (ref "R47")
      (value "68K 0.1%")
      (footprint "easyedapro:R0603")
      (libsource (lib "easyedapro") (part "电阻"))
    )
    (comp (ref "R48")
      (value "68K 0.1%")
      (footprint "easyedapro:R0603")
      (libsource (lib "easyedapro") (part "电阻"))
    )
    (comp (ref "R49") (value "10K") (footprint "easyedapro:R0603") (libsource (lib "easyedapro") (part "电阻")))
    (comp (ref "R50") (value "10K") (footprint "easyedapro:R0603") (libsource (lib "easyedapro") (part "电阻")))
    (comp (ref "R51") (value "2.2") (footprint "easyedapro:R0603") (libsource (lib "easyedapro") (part "电阻")))
    (comp (ref "R52") (value "2.2") (footprint "easyedapro:R0603") (libsource (lib "easyedapro") (part "电阻")))
    (comp (ref "R53") (value "1M") (footprint "easyedapro:R0603") (libsource (lib "easyedapro") (part "电阻")))
    (comp (ref "R54") (value "51K") (footprint "easyedapro:R0603") (libsource (lib "easyedapro") (part "电阻")))
    (comp (ref "R55") (value "200") (footprint "easyedapro:R0603") (libsource (lib "easyedapro") (part "电阻")))
    (comp (ref "R56") (value "1K") (footprint "easyedapro:R0603") (libsource (lib "easyedapro") (part "电阻")))
    (comp (ref "R57")
      (value "4.7K")
      (footprint "easyedapro:R0603")
      (libsource (lib "easyedapro") (part "电阻"))
    )
    (comp (ref "R58") (value "10K") (footprint "easyedapro:R0603") (libsource (lib "easyedapro") (part "电阻")))
    (comp (ref "R59") (value "10K") (footprint "easyedapro:R0603") (libsource (lib "easyedapro") (part "电阻")))
    (comp (ref "R72")
      (value "NCP18XH103F03RB")
      (footprint "easyedapro:R0603")
      (description "阻值(25°C):10kΩ;B值(25°C/50°C):3380K;电阻精度:±1%;功率:100mW;B值精度:±1%;最大稳态电流(25°C):310uA;")
      (fields (field (name "Manufacturer") "muRata(村田)"))
      (libsource (lib "easyedapro") (part "NCP18XH103F03RB"))
    )
    (comp (ref "R73") (value "1K") (footprint "easyedapro:R0603") (libsource (lib "easyedapro") (part "电阻")))
    (comp (ref "R78") (value "0") (footprint "easyedapro:R0603") (libsource (lib "easyedapro") (part "电阻")))
    (comp (ref "SCREW4")
      (value "~")
      (footprint "easyedapro:M3螺丝")
      (libsource (lib "easyedapro") (part "螺丝孔"))
    )
    (comp (ref "U1")
      (value "CSD18536KTT")
      (footprint "easyedapro:TO-263-3_L10.4-W10.1-P5.08-LS15.4")
      (fields (field (name "Manufacturer") "TI(德州仪器)"))
      (libsource (lib "easyedapro") (part "CSD18536KTT"))
    )
    (comp (ref "U2")
      (value "LM5050MKX-1/NOPB")
      (footprint "easyedapro:TSOT-23-6_L2.9-W1.6-P0.95-LS2.8-BL")
      (description "LM5050-1 5V 至 75V、400uA IQ ORing FET 控制器")
      (fields (field (name "Manufacturer") "TI(德州仪器)"))
      (libsource (lib "easyedapro") (part "LM5050MKX-1/NOPB"))
    )
    (comp (ref "U3")
      (value "CH224K")
      (footprint "easyedapro:ESSOP-10_L4.9-W3.9-P1.0-LS6.0-TL-EP")
      (fields (field (name "Manufacturer") "WCH(南京沁恒)"))
      (libsource (lib "easyedapro") (part "CH224K"))
    )
    (comp (ref "U4")
      (value "ME3121AM6G")
      (footprint "easyedapro:SOT-23-6_L2.9-W1.6-P0.95-LS2.8-BR")
      (description "功能类型:降压型;输出类型:可调;工作电压:4.7V~40V;输出电压:-;输出电流:-;")
      (fields (field (name "Manufacturer") "MICRONE(南京微盟)"))
      (libsource (lib "easyedapro") (part "ME3121AM6G"))
    )
    (comp (ref "U5")
      (value "SY8120IABC")
      (footprint "easyedapro:SOT-23-6_L2.9-W1.6-P0.95-LS2.8-BL")
      (description "功能类型:降压型;输出类型:-;工作电压:4.2V~18V;输出电压:3.3V;输出电流:2A;")
      (fields (field (name "Manufacturer") "silergy(矽力杰)"))
      (libsource (lib "easyedapro") (part "SY8120IABC"))
    )
    (comp (ref "U6")
      (value "LM5175PWPR")
      (footprint "easyedapro:HTSSOP-28_L9.8-W4.5-P0.65-LS6.6-BL-EP")
      (description "功能类型:升降压型;输出类型:-;工作电压:3.5V~42V;输出电压:-;输出电流:-;")
      (fields (field (name "Manufacturer") "TI(德州仪器)"))
      (libsource (lib "easyedapro") (part "LM5175PWPR"))
    )
    (comp (ref "U7")
      (value "CSD18536KTT")
      (footprint "easyedapro:TO-263-3_L10.4-W10.1-P5.08-LS15.4")
      (fields (field (name "Manufacturer") "TI(德州仪器)"))
      (libsource (lib "easyedapro") (part "CSD18536KTT"))
    )
    (comp (ref "U8")
      (value "CSD18536KTT")
      (footprint "easyedapro:TO-263-3_L10.4-W10.1-P5.08-LS15.4")
      (fields (field (name "Manufacturer") "TI(德州仪器)"))
      (libsource (lib "easyedapro") (part "CSD18536KTT"))
    )
    (comp (ref "U9")
      (value "CSD18536KTT")
      (footprint "easyedapro:TO-263-3_L10.4-W10.1-P5.08-LS15.4")
      (fields (field (name "Manufacturer") "TI(德州仪器)"))
      (libsource (lib "easyedapro") (part "CSD18536KTT"))
    )
    (comp (ref "U10")
      (value "INA240A2PWR")
      (footprint "easyedapro:TSSOP-8_L4.4-W3.0-P0.65-LS6.4-BL")
      (description "放大器数:单路;")
      (fields (field (name "Manufacturer") "TI(德州仪器)"))
      (libsource (lib "easyedapro") (part "INA240A2PWR"))
    )
    (comp (ref "U11")
      (value "RS8552XM")
      (footprint "easyedapro:MSOP-8_L3.0-W3.0-P0.65-LS4.9-BL")
      (description "放大器数:双路;增益带宽积(GBP):4.5MHz;压摆率(SR):2.5V/us;")
      (fields (field (name "Manufacturer") "RUNIC(润石)"))
      (libsource (lib "easyedapro") (part "RS8552XM"))
    )
    (comp (ref "U12")
      (value "TL431AIDBZR")
      (footprint "easyedapro:SOT-23-3_L2.9-W1.6-P1.90-LS2.8-BR")
      (description "输出类型:可调;输入电压:-;输出电压:2.495V~36V;输出电流:100mA;精度:±1%;")
      (fields (field (name "Manufacturer") "TI(德州仪器)"))
      (libsource (lib "easyedapro") (part "TL431AIDBZR"))
    )
    (comp (ref "U18")
      (value "CSD18536KTT")
      (footprint "easyedapro:TO-263-3_L10.4-W10.1-P5.08-LS15.4")
      (fields (field (name "Manufacturer") "TI(德州仪器)"))
      (libsource (lib "easyedapro") (part "CSD18536KTT"))
    )
    (comp (ref "U19")
      (value "CSD18536KTT")
      (footprint "easyedapro:TO-263-3_L10.4-W10.1-P5.08-LS15.4")
      (fields (field (name "Manufacturer") "TI(德州仪器)"))
      (libsource (lib "easyedapro") (part "CSD18536KTT"))
    )
    (comp (ref "USB1")
      (value "KH-TYPE-C-16P")
      (footprint "easyedapro:USB-C-SMD_KH-TYPE-C-16P")
      (description "连接器类型:Type-C;标准:-;公母:母;端口数量:1;触点数量:16P;安装方式:卧贴;额定电流 - 电源:3A;工作温度范围:-40°C~+85°C;")
      (fields (field (name "Manufacturer") "kinghelm(金航标)"))
      (libsource (lib "easyedapro") (part "KH-TYPE-C-16P"))
    )
    (comp (ref "BUZZER1")
      (value "2.7kHz")
      (footprint "easyedapro:BUZ-SMD_4P-L8.5-W8.5-P8.50-BR")
      (description "驱动方式:无源(外部驱动);构造类型:电磁式;频率:2.7kHz;声压(SPL):80dB;")
      (fields (field (name "Manufacturer Part") "MLT-8530") (field (name "Manufacturer") "华能"))
      (libsource (lib "easyedapro") (part "MLT-8530"))
    )
    (comp (ref "C62")
      (value "100nF")
      (footprint "easyedapro:C0603")
      (libsource (lib "easyedapro") (part "CapAcitance"))
    )
    (comp (ref "C63")
      (value "10uF")
      (footprint "easyedapro:C0603")
      (libsource (lib "easyedapro") (part "CapAcitance"))
    )
    (comp (ref "C64")
      (value "100nF")
      (footprint "easyedapro:C0603")
      (libsource (lib "easyedapro") (part "CapAcitance"))
    )
    (comp (ref "C65")
      (value "100nF")
      (footprint "easyedapro:C0603")
      (libsource (lib "easyedapro") (part "CapAcitance"))
    )
    (comp (ref "C66")
      (value "100nF")
      (footprint "easyedapro:C0603")
      (libsource (lib "easyedapro") (part "CapAcitance"))
    )
    (comp (ref "C67")
      (value "10nF")
      (footprint "easyedapro:C0603")
      (libsource (lib "easyedapro") (part "CapAcitance"))
    )
    (comp (ref "C68")
      (value "1uF")
      (footprint "easyedapro:C0603")
      (libsource (lib "easyedapro") (part "CapAcitance"))
    )
    (comp (ref "C69")
      (value "1uF")
      (footprint "easyedapro:C0603")
      (libsource (lib "easyedapro") (part "CapAcitance"))
    )
    (comp (ref "C70")
      (value "100nF")
      (footprint "easyedapro:C0603")
      (libsource (lib "easyedapro") (part "CapAcitance"))
    )
    (comp (ref "C71")
      (value "10uF")
      (footprint "easyedapro:C0603")
      (libsource (lib "easyedapro") (part "CapAcitance"))
    )
    (comp (ref "C72")
      (value "100nF")
      (footprint "easyedapro:C0603")
      (libsource (lib "easyedapro") (part "CapAcitance"))
    )
    (comp (ref "C73")
      (value "10uF")
      (footprint "easyedapro:C0603")
      (libsource (lib "easyedapro") (part "CapAcitance"))
    )
    (comp (ref "C74")
      (value "10uF")
      (footprint "easyedapro:C0603")
      (libsource (lib "easyedapro") (part "CapAcitance"))
    )
    (comp (ref "C75")
      (value "100nF")
      (footprint "easyedapro:C0603")
      (libsource (lib "easyedapro") (part "CapAcitance"))
    )
    (comp (ref "C76")
      (value "100nF")
      (footprint "easyedapro:C0603")
      (libsource (lib "easyedapro") (part "CapAcitance"))
    )
    (comp (ref "C77")
      (value "100nF")
      (footprint "easyedapro:C0603")
      (libsource (lib "easyedapro") (part "CapAcitance"))
    )
    (comp (ref "C78")
      (value "100nF")
      (footprint "easyedapro:C0603")
      (libsource (lib "easyedapro") (part "CapAcitance"))
    )
    (comp (ref "C80")
      (value "100nF")
      (footprint "easyedapro:C0603")
      (libsource (lib "easyedapro") (part "CapAcitance"))
    )
    (comp (ref "CN3")
      (value "ZX-XH2.54-2PZZ")
      (footprint "easyedapro:CONN-TH_2P-P2.50_HX25003-2A")
      (fields (field (name "Manufacturer") "Megastar(兆星)"))
      (libsource (lib "easyedapro") (part "ZX-XH2.54-2PZZ"))
    )
    (comp (ref "D15")
      (value "1N4148WT")
      (footprint "easyedapro:SOD-523_L1.2-W0.8-LS1.6-RD")
      (description "二极管配置:独立式;正向压降(Vf):1V@10mA;直流反向耐压(Vr):75V;整流电流:300mA;反向恢复时间(trr):4ns;")
      (fields (field (name "Manufacturer") "onsemi(安森美)"))
      (libsource (lib "easyedapro") (part "1N4148WT_C232841"))
    )
    (comp (ref "D16")
      (value "1N4148WT")
      (footprint "easyedapro:SOD-523_L1.2-W0.8-LS1.6-RD")
      (description "二极管配置:独立式;正向压降(Vf):1V@10mA;直流反向耐压(Vr):75V;整流电流:300mA;反向恢复时间(trr):4ns;")
      (fields (field (name "Manufacturer") "onsemi(安森美)"))
      (libsource (lib "easyedapro") (part "1N4148WT_C232841"))
    )
    (comp (ref "D17")
      (value "1N4148WT")
      (footprint "easyedapro:SOD-523_L1.2-W0.8-LS1.6-RD")
      (description "二极管配置:独立式;正向压降(Vf):1V@10mA;直流反向耐压(Vr):75V;整流电流:300mA;反向恢复时间(trr):4ns;")
      (fields (field (name "Manufacturer") "onsemi(安森美)"))
      (libsource (lib "easyedapro") (part "1N4148WT_C232841"))
    )
    (comp (ref "D18")
      (value "1N4148WT")
      (footprint "easyedapro:SOD-523_L1.2-W0.8-LS1.6-RD")
      (description "二极管配置:独立式;正向压降(Vf):1V@10mA;直流反向耐压(Vr):75V;整流电流:300mA;反向恢复时间(trr):4ns;")
      (fields (field (name "Manufacturer") "onsemi(安森美)"))
      (libsource (lib "easyedapro") (part "1N4148WT_C232841"))
    )
    (comp (ref "D19")
      (value "1N4148WT")
      (footprint "easyedapro:SOD-523_L1.2-W0.8-LS1.6-RD")
      (description "二极管配置:独立式;正向压降(Vf):1V@10mA;直流反向耐压(Vr):75V;整流电流:300mA;反向恢复时间(trr):4ns;")
      (fields (field (name "Manufacturer") "onsemi(安森美)"))
      (libsource (lib "easyedapro") (part "1N4148WT_C232841"))
    )
    (comp (ref "D20")
      (value "1N4148WT")
      (footprint "easyedapro:SOD-523_L1.2-W0.8-LS1.6-RD")
      (description "二极管配置:独立式;正向压降(Vf):1V@10mA;直流反向耐压(Vr):75V;整流电流:300mA;反向恢复时间(trr):4ns;")
      (fields (field (name "Manufacturer") "onsemi(安森美)"))
      (libsource (lib "easyedapro") (part "1N4148WT_C232841"))
    )
    (comp (ref "FPC1")
      (value "AFC01-S10FCA-00")
      (footprint "easyedapro:FPC-SMD_P0.5-10P_FGS-XJ-H2.0")
      (description "锁定特性:翻盖式;触点类型:下接;触点数量:10P;间距:0.5mm;安装类型:卧贴;")
      (fields (field (name "Manufacturer") "JS(钜硕电子)"))
      (libsource (lib "easyedapro") (part "AFC01-S10FCA-00"))
    )
    (comp (ref "L5")
      (value "AN2051-245")
      (footprint "easyedapro:ANT2051")
      (description "小体积，高增益，WIFI，蓝牙，zigBee 2.4G天线")
      (fields (field (name "Manufacturer") "rainsun(霖昱微)"))
      (libsource (lib "easyedapro") (part "AN2051-245"))
    )
    (comp (ref "LED2")
      (value "~")
      (footprint "easyedapro:LED_0603")
      (libsource (lib "easyedapro") (part "LED_R"))
    )
    (comp (ref "LED3")
      (value "~")
      (footprint "easyedapro:LED_0603")
      (libsource (lib "easyedapro") (part "LED_G"))
    )
    (comp (ref "Q6")
      (value "BC847BDW1T1G")
      (footprint "easyedapro:SOT-363_L2.0-W1.3-P0.65-LS2.1-TL")
      (description "晶体管类型:NPN;集电极电流(Ic):100mA;集射极击穿电压(Vceo):45V;功率(Pd):380mW;直流电流增益(hFE@Ic,Vce):150@10uA,5.0V;")
      (fields (field (name "Manufacturer") "onsemi(安森美)"))
      (libsource (lib "easyedapro") (part "BC847BDW1T1G"))
    )
    (comp (ref "Q7")
      (value "S8050")
      (footprint "easyedapro:SOT-23-3_L2.9-W1.3-P1.90-LS2.3-BR")
      (description "晶体管类型:NPN;集电极电流(Ic):500mA;集射极击穿电压(Vceo):25V;耗散功率(Pd):300mW;直流电流增益(hFE):120@50mA,1.0V;")
      (fields (field (name "Manufacturer") "宏嘉诚"))
      (libsource (lib "easyedapro") (part "S8050_C20069125"))
    )
    (comp (ref "Q8")
      (value "SI2306")
      (footprint "easyedapro:SOT-23-3_L2.9-W1.4-P1.91-LS2.6-BR")
      (fields (field (name "Manufacturer") "TWGMC(台湾迪嘉)"))
      (libsource (lib "easyedapro") (part "SI2306_C727154"))
    )
    (comp (ref "Q9")
      (value "S8050")
      (footprint "easyedapro:SOT-23-3_L2.9-W1.3-P1.90-LS2.3-BR")
      (description "晶体管类型:NPN;集电极电流(Ic):500mA;集射极击穿电压(Vceo):25V;耗散功率(Pd):300mW;直流电流增益(hFE):120@50mA,1.0V;")
      (fields (field (name "Manufacturer") "宏嘉诚"))
      (libsource (lib "easyedapro") (part "S8050_C20069125"))
    )
    (comp (ref "R60") (value "0") (footprint "easyedapro:R0603") (libsource (lib "easyedapro") (part "电阻")))
    (comp (ref "R61") (value "10K") (footprint "easyedapro:R0603") (libsource (lib "easyedapro") (part "电阻")))
    (comp (ref "R62") (value "1K") (footprint "easyedapro:R0603") (libsource (lib "easyedapro") (part "电阻")))
    (comp (ref "R63") (value "1K") (footprint "easyedapro:R0603") (libsource (lib "easyedapro") (part "电阻")))
    (comp (ref "R64")
      (value "1M 0.1%")
      (footprint "easyedapro:R0603")
      (libsource (lib "easyedapro") (part "电阻"))
    )
    (comp (ref "R65")
      (value "68K 0.1%")
      (footprint "easyedapro:R0603")
      (libsource (lib "easyedapro") (part "电阻"))
    )
    (comp (ref "R66") (value "0") (footprint "easyedapro:R0603") (libsource (lib "easyedapro") (part "电阻")))
    (comp (ref "R67") (value "10K") (footprint "easyedapro:R0603") (libsource (lib "easyedapro") (part "电阻")))
    (comp (ref "R68") (value "10K") (footprint "easyedapro:R0603") (libsource (lib "easyedapro") (part "电阻")))
    (comp (ref "R69") (value "10K") (footprint "easyedapro:R0603") (libsource (lib "easyedapro") (part "电阻")))
    (comp (ref "R70") (value "470") (footprint "easyedapro:R0603") (libsource (lib "easyedapro") (part "电阻")))
    (comp (ref "R71") (value "1K") (footprint "easyedapro:R0603") (libsource (lib "easyedapro") (part "电阻")))
    (comp (ref "R74") (value "470") (footprint "easyedapro:R0603") (libsource (lib "easyedapro") (part "电阻")))
    (comp (ref "R75") (value "10K") (footprint "easyedapro:R0603") (libsource (lib "easyedapro") (part "电阻")))
    (comp (ref "R76") (value "510") (footprint "easyedapro:R0603") (libsource (lib "easyedapro") (part "电阻")))
    (comp (ref "R77") (value "510") (footprint "easyedapro:R0603") (libsource (lib "easyedapro") (part "电阻")))
    (comp (ref "SCREW2")
      (value "~")
      (footprint "easyedapro:M3螺丝")
      (libsource (lib "easyedapro") (part "螺丝孔"))
    )
    (comp (ref "SCREW3")
      (value "~")
      (footprint "easyedapro:M3螺丝")
      (libsource (lib "easyedapro") (part "螺丝孔"))
    )
    (comp (ref "SW1")
      (value "EC11E18244AU")
      (footprint "easyedapro:SW-TH_EC11XXXXXXXX")
      (fields (field (name "Manufacturer") "ALPSALPINE(阿尔卑斯阿尔派)"))
      (libsource (lib "easyedapro") (part "EC11E18244AU"))
    )
    (comp (ref "SW2")
      (value "TS-1010-C-A")
      (footprint "easyedapro:KEY-SMD_TX-1010-X-X")
      (fields (field (name "Manufacturer") "XKB Connectivity(中国星坤)"))
      (libsource (lib "easyedapro") (part "TS-1010-C-A"))
    )
    (comp (ref "U13")
      (value "ESP32-PICO-D4")
      (footprint "easyedapro:LGA-48_L7.0-W7.0-P0.50-BL-EP5.4")
      (description "频率范围:2.412GHz~2.484GHz;接口:I2C,SPI;应用领域:IoT；WiFi；蓝牙;数据速率:150Mbps;灵敏度:-97dBm;典型应用频率:2.4GHz;")
      (fields (field (name "Manufacturer") "ESPRESSIF(乐鑫)"))
      (libsource (lib "easyedapro") (part "ESP32-PICO-D4"))
    )
    (comp (ref "U14")
      (value "CH340C")
      (footprint "easyedapro:SOP-16_L10.0-W3.9-P1.27-LS6.0-BL")
      (description "应用功能:收发器;接口协议:USB 2.0;数据速率:2Mbps;")
      (fields (field (name "Manufacturer") "WCH(南京沁恒)"))
      (libsource (lib "easyedapro") (part "CH340C"))
    )
    (comp (ref "U15")
      (value "REF3033AIDBZR")
      (footprint "easyedapro:SOT-23-3_L3.0-W1.7-P0.95-LS2.9-BR")
      (description "输出类型:固定;输入电压:3.35V~5.5V;输出电压:3.3V;输出电流:25mA;精度:±0.2%;")
      (fields (field (name "Manufacturer") "TI(德州仪器)"))
      (libsource (lib "easyedapro") (part "REF3033AIDBZR"))
    )
    (comp (ref "U16")
      (value "DAC8562SDGSR")
      (footprint "easyedapro:VSSOP-10_L3.0-W3.0-P0.50-LS4.9-BL")
      (description "DAC8562 具有 2.5V、4ppm/°C 基准的 16 位、双通道、低功耗、超低毛刺脉冲、电压输出 DAC")
      (fields (field (name "Manufacturer") "TI(德州仪器)"))
      (libsource (lib "easyedapro") (part "DAC8562SDGSR"))
    )
    (comp (ref "U20")
      (value "WAFER-SH1.0-2PWB")
      (footprint "easyedapro:CONN-SMD_2P-P1.00_XUNPU_WAFER-SH1.0-2PWB")
      (fields (field (name "Manufacturer") "XUNPU(讯普)"))
      (libsource (lib "easyedapro") (part "WAFER-SH1.0-2PWB"))
    )
  )
  (nets
    (net (code "1") (name "-0.6V") (class "Default")
      (node (ref "C55") (pin "1") (pinfunction "1_1") (pintype "input"))
      (node (ref "C59") (pin "1") (pinfunction "1_1") (pintype "input"))
      (node (ref "C60") (pin "1") (pinfunction "1_1") (pintype "input"))
      (node (ref "Q5") (pin "2") (pinfunction "E_2") (pintype "unspecified"))
      (node (ref "R43") (pin "1") (pinfunction "1_1") (pintype "input"))
      (node (ref "U10") (pin "4") (pinfunction "GND_4") (pintype "unspecified"))
      (node (ref "U11") (pin "4") (pinfunction "V-_4") (pintype "unspecified"))
    )
    (net (code "2") (name "-2V") (class "Default")
      (node (ref "C71") (pin "1") (pinfunction "1_1") (pintype "input"))
      (node (ref "C73") (pin "1") (pinfunction "1_1") (pintype "input"))
      (node (ref "D16") (pin "2") (pinfunction "A_2") (pintype "unspecified"))
      (node (ref "D18") (pin "2") (pinfunction "A_2") (pintype "unspecified"))
      (node (ref "Q5") (pin "3") (pinfunction "C_3") (pintype "unspecified"))
      (node (ref "R59") (pin "1") (pinfunction "1_1") (pintype "input"))
    )
    (net (code "3") (name "3.3A") (class "Default")
      (node (ref "C62") (pin "2") (pinfunction "2_2") (pintype "input"))
      (node (ref "C63") (pin "2") (pinfunction "2_2") (pintype "input"))
      (node (ref "R60") (pin "1") (pinfunction "1_1") (pintype "input"))
      (node (ref "U13") (pin "1") (pinfunction "VDDA_1") (pintype "unspecified"))
      (node (ref "U13") (pin "19") (pinfunction "VDD3P3_RTC_19") (pintype "unspecified"))
      (node (ref "U13") (pin "3") (pinfunction "VDDA3P3_3") (pintype "unspecified"))
      (node (ref "U13") (pin "37") (pinfunction "VDD3P3_CPU_37") (pintype "unspecified"))
      (node (ref "U13") (pin "4") (pinfunction "VDDA3P3_4") (pintype "unspecified"))
      (node (ref "U13") (pin "43") (pinfunction "VDDA_43") (pintype "unspecified"))
      (node (ref "U13") (pin "46") (pinfunction "VDDA_46") (pintype "unspecified"))
    )
    (net (code "4") (name "3.3V") (class "Default")
      (node (ref "BUZZER1") (pin "1") (pinfunction "+_1") (pintype "unspecified"))
      (node (ref "C17") (pin "2") (pinfunction "2_2") (pintype "unspecified"))
      (node (ref "C19") (pin "2") (pinfunction "2_2") (pintype "input"))
      (node (ref "C21") (pin "2") (pinfunction "2_2") (pintype "input"))
      (node (ref "C55") (pin "2") (pinfunction "2_2") (pintype "input"))
      (node (ref "C59") (pin "2") (pinfunction "2_2") (pintype "input"))
      (node (ref "C65") (pin "2") (pinfunction "2_2") (pintype "input"))
      (node (ref "C66") (pin "2") (pinfunction "2_2") (pintype "input"))
      (node (ref "C68") (pin "2") (pinfunction "2_2") (pintype "input"))
      (node (ref "C75") (pin "2") (pinfunction "2_2") (pintype "input"))
      (node (ref "D19") (pin "1") (pinfunction "C_1") (pintype "unspecified"))
      (node (ref "FPC1") (pin "2") (pinfunction "2_2") (pintype "unspecified"))
      (node (ref "FPC1") (pin "8") (pinfunction "8_8") (pintype "unspecified"))
      (node (ref "FPC1") (pin "9") (pinfunction "9_9") (pintype "unspecified"))
      (node (ref "L2") (pin "2") (pinfunction "2_2") (pintype "unspecified"))
      (node (ref "Q3") (pin "2") (pinfunction "E_2") (pintype "input"))
      (node (ref "R56") (pin "1") (pinfunction "1_1") (pintype "input"))
      (node (ref "R60") (pin "2") (pinfunction "2_2") (pintype "input"))
      (node (ref "R61") (pin "2") (pinfunction "2_2") (pintype "input"))
      (node (ref "R67") (pin "2") (pinfunction "2_2") (pintype "input"))
      (node (ref "R68") (pin "1") (pinfunction "1_1") (pintype "input"))
      (node (ref "R69") (pin "2") (pinfunction "2_2") (pintype "input"))
      (node (ref "R7") (pin "2") (pinfunction "2_2") (pintype "input"))
      (node (ref "R73") (pin "2") (pinfunction "2_2") (pintype "input"))
      (node (ref "R75") (pin "2") (pinfunction "2_2") (pintype "input"))
      (node (ref "U10") (pin "5") (pinfunction "VS_5") (pintype "unspecified"))
      (node (ref "U11") (pin "8") (pinfunction "V+_8") (pintype "unspecified"))
      (node (ref "U14") (pin "16") (pinfunction "VCC_16") (pintype "unspecified"))
      (node (ref "U14") (pin "4") (pinfunction "V3_4") (pintype "unspecified"))
      (node (ref "U15") (pin "1") (pinfunction "IN_1") (pintype "unspecified"))
      (node (ref "U16") (pin "9") (pinfunction "AVDD_9") (pintype "unspecified"))
    )
    (net (code "5") (name "9V") (class "Default")
      (node (ref "C13") (pin "2") (pinfunction "2_2") (pintype "input"))
      (node (ref "C14") (pin "2") (pinfunction "2_2") (pintype "unspecified"))
      (node (ref "C15") (pin "2") (pinfunction "2_2") (pintype "input"))
      (node (ref "C20") (pin "2") (pinfunction "2_2") (pintype "unspecified"))
      (node (ref "C35") (pin "2") (pinfunction "2_2") (pintype "input"))
      (node (ref "CN3") (pin "1") (pinfunction "1_1") (pintype "unspecified"))
      (node (ref "D20") (pin "1") (pinfunction "C_1") (pintype "unspecified"))
      (node (ref "L1") (pin "2") (pinfunction "2_2") (pintype "unspecified"))
      (node (ref "R6") (pin "2") (pinfunction "2_2") (pintype "input"))
      (node (ref "U5") (pin "4") (pinfunction "EN_4") (pintype "unspecified"))
      (node (ref "U5") (pin "5") (pinfunction "IN_5") (pintype "unspecified"))
      (node (ref "U6") (pin "24") (pinfunction "BIAS_24") (pintype "unspecified"))
    )
    (net (code "6") (name "AGND") (class "Default")
      (node (ref "C56") (pin "1") (pinfunction "1_1") (pintype "input"))
      (node (ref "C60") (pin "2") (pinfunction "2_2") (pintype "input"))
      (node (ref "C61") (pin "2") (pinfunction "2_2") (pintype "input"))
      (node (ref "C67") (pin "1") (pinfunction "1_1") (pintype "input"))
      (node (ref "C68") (pin "1") (pinfunction "1_1") (pintype "input"))
      (node (ref "C69") (pin "1") (pinfunction "1_1") (pintype "input"))
      (node (ref "C71") (pin "2") (pinfunction "2_2") (pintype "input"))
      (node (ref "C73") (pin "2") (pinfunction "2_2") (pintype "input"))
      (node (ref "C74") (pin "1") (pinfunction "1_1") (pintype "input"))
      (node (ref "C75") (pin "1") (pinfunction "1_1") (pintype "input"))
      (node (ref "C79") (pin "1") (pinfunction "1_1") (pintype "input"))
      (node (ref "D13") (pin "2") (pinfunction "A_2") (pintype "unspecified"))
      (node (ref "D15") (pin "1") (pinfunction "C_1") (pintype "unspecified"))
      (node (ref "D17") (pin "1") (pinfunction "C_1") (pintype "unspecified"))
      (node (ref "R48") (pin "2") (pinfunction "2_2") (pintype "input"))
      (node (ref "R65") (pin "2") (pinfunction "2_2") (pintype "input"))
      (node (ref "R72") (pin "1") (pinfunction "1_1") (pintype "input"))
      (node (ref "R78") (pin "1") (pinfunction "1_1") (pintype "input"))
      (node (ref "U10") (pin "6") (pinfunction "REF2_6") (pintype "unspecified"))
      (node (ref "U10") (pin "7") (pinfunction "REF1_7") (pintype "unspecified"))
      (node (ref "U15") (pin "3") (pinfunction "GND_3") (pintype "unspecified"))
      (node (ref "U16") (pin "3") (pinfunction "GND_3") (pintype "unspecified"))
    )
    (net (code "7") (name "BOOT1") (class "Default")
      (node (ref "C30") (pin "2") (pinfunction "2_2") (pintype "input"))
      (node (ref "D23") (pin "1") (pinfunction "K_1") (pintype "unspecified"))
      (node (ref "U6") (pin "26") (pinfunction "BOOT1_26") (pintype "unspecified"))
    )
    (net (code "8") (name "BOOT2") (class "Default")
      (node (ref "C31") (pin "2") (pinfunction "2_2") (pintype "input"))
      (node (ref "D24") (pin "1") (pinfunction "K_1") (pintype "unspecified"))
      (node (ref "U6") (pin "20") (pinfunction "BOOT2_20") (pintype "unspecified"))
    )
    (net (code "9") (name "BTN") (class "Default")
      (node (ref "C80") (pin "2") (pinfunction "2_2") (pintype "input"))
      (node (ref "R75") (pin "1") (pinfunction "1_1") (pintype "input"))
      (node (ref "SW2") (pin "2") (pinfunction "2_2") (pintype "unspecified"))
      (node (ref "U13") (pin "6") (pinfunction "SENSOR_CAPP_6") (pintype "unspecified"))
    )
    (net (code "10") (name "BUZZER") (class "Default")
      (node (ref "R70") (pin "1") (pinfunction "1_1") (pintype "input"))
      (node (ref "U13") (pin "21") (pinfunction "IO15_21") (pintype "unspecified"))
    )
    (net (code "11") (name "CC1") (class "Default")
      (node (ref "U3") (pin "7") (pinfunction "CC1_7") (pintype "unspecified"))
      (node (ref "USB1") (pin "A5") (pinfunction "CC1_A5") (pintype "unspecified"))
    )
    (net (code "12") (name "CC2") (class "Default")
      (node (ref "U3") (pin "6") (pinfunction "CC2_6") (pintype "unspecified"))
      (node (ref "USB1") (pin "B5") (pinfunction "CC2_B5") (pintype "unspecified"))
    )
    (net (code "13") (name "CC_LOOP") (class "Default")
      (node (ref "C58") (pin "2") (pinfunction "2_2") (pintype "input"))
      (node (ref "D8") (pin "2") (pinfunction "K_2") (pintype "unspecified"))
      (node (ref "R44") (pin "2") (pinfunction "2_2") (pintype "input"))
      (node (ref "U11") (pin "7") (pinfunction "OUT_2_7") (pintype "output"))
      (node (ref "U13") (pin "7") (pinfunction "SENSOR_CAPN_7") (pintype "unspecified"))
    )
    (net (code "14") (name "COMP") (class "Default")
      (node (ref "C27") (pin "2") (pinfunction "2_2") (pintype "input"))
      (node (ref "D8") (pin "1") (pinfunction "A_1") (pintype "unspecified"))
      (node (ref "Q4") (pin "3") (pinfunction "C_3") (pintype "input"))
      (node (ref "R17") (pin "2") (pinfunction "2_2") (pintype "input"))
      (node (ref "U6") (pin "9") (pinfunction "COMP_9") (pintype "unspecified"))
    )
    (net (code "15") (name "CS") (class "Default")
      (node (ref "D5") (pin "2") (pinfunction "A_2") (pintype "unspecified"))
      (node (ref "R18") (pin "2") (pinfunction "2_2") (pintype "input"))
      (node (ref "R21") (pin "1") (pinfunction "1_1") (pintype "input"))
      (node (ref "R23") (pin "1") (pinfunction "1_1") (pintype "input"))
      (node (ref "R24") (pin "2") (pinfunction "2_2") (pintype "unspecified"))
      (node (ref "R25") (pin "2") (pinfunction "2_2") (pintype "unspecified"))
      (node (ref "R26") (pin "2") (pinfunction "2_2") (pintype "unspecified"))
      (node (ref "U1") (pin "3") (pinfunction "S_3") (pintype "unspecified"))
      (node (ref "U8") (pin "3") (pinfunction "S_3") (pintype "unspecified"))
    )
    (net (code "16") (name "CS_N") (class "Default")
      (node (ref "C29") (pin "1") (pinfunction "1_1") (pintype "input"))
      (node (ref "R19") (pin "1") (pinfunction "1_1") (pintype "input"))
      (node (ref "U6") (pin "15") (pinfunction "CSG_15") (pintype "unspecified"))
    )
    (net (code "17") (name "CS_P") (class "Default")
      (node (ref "C29") (pin "2") (pinfunction "2_2") (pintype "input"))
      (node (ref "R18") (pin "1") (pinfunction "1_1") (pintype "input"))
      (node (ref "U6") (pin "16") (pinfunction "CS_16") (pintype "unspecified"))
    )
    (net (code "18") (name "DAC_CLR") (class "Default")
      (node (ref "U13") (pin "18") (pinfunction "IO12_18") (pintype "unspecified"))
      (node (ref "U16") (pin "5") (pinfunction "CLR#_5") (pintype "unspecified"))
    )
    (net (code "19") (name "DAC_CS") (class "Default")
      (node (ref "U13") (pin "34") (pinfunction "IO5_34") (pintype "unspecified"))
      (node (ref "U16") (pin "6") (pinfunction "SYNC_6") (pintype "unspecified"))
    )
    (net (code "20") (name "DAC_LDAC") (class "Default")
      (node (ref "U13") (pin "20") (pinfunction "IO13_20") (pintype "unspecified"))
      (node (ref "U16") (pin "4") (pinfunction "LDAC#_4") (pintype "unspecified"))
    )
    (net (code "21") (name "DTR") (class "Default")
      (node (ref "Q6") (pin "4") (pinfunction "E_4") (pintype "unspecified"))
      (node (ref "R62") (pin "2") (pinfunction "2_2") (pintype "input"))
      (node (ref "U14") (pin "13") (pinfunction "DTR#_13") (pintype "unspecified"))
    )
    (net (code "22") (name "D{slash}C") (class "Default")
      (node (ref "FPC1") (pin "4") (pinfunction "4_4") (pintype "unspecified"))
      (node (ref "U13") (pin "15") (pinfunction "IO26_15") (pintype "unspecified"))
    )
    (net (code "23") (name "EC11_S1") (class "Default")
      (node (ref "C78") (pin "2") (pinfunction "2_2") (pintype "input"))
      (node (ref "R67") (pin "1") (pinfunction "1_1") (pintype "input"))
      (node (ref "SW1") (pin "D") (pinfunction "D_D") (pintype "unspecified"))
      (node (ref "U13") (pin "38") (pinfunction "IO19_38") (pintype "unspecified"))
    )
    (net (code "24") (name "EN") (class "Default")
      (node (ref "C64") (pin "2") (pinfunction "2_2") (pintype "input"))
      (node (ref "Q6") (pin "6") (pinfunction "C_6") (pintype "unspecified"))
      (node (ref "R61") (pin "1") (pinfunction "1_1") (pintype "input"))
      (node (ref "U13") (pin "9") (pinfunction "EN_9") (pintype "unspecified"))
    )
    (net (code "25") (name "FAN") (class "Default")
      (node (ref "R71") (pin "1") (pinfunction "1_1") (pintype "input"))
      (node (ref "U13") (pin "24") (pinfunction "IO4_24") (pintype "unspecified"))
    )
    (net (code "26") (name "GND") (class "Default")
      (node (ref "BUZZER1") (pin "3") (pinfunction "3_3") (pintype "unspecified"))
      (node (ref "BUZZER1") (pin "4") (pinfunction "4_4") (pintype "unspecified"))
      (node (ref "C1") (pin "1") (pinfunction "1_1") (pintype "input"))
      (node (ref "C10") (pin "1") (pinfunction "1_1") (pintype "input"))
      (node (ref "C11") (pin "1") (pinfunction "1_1") (pintype "input"))
      (node (ref "C14") (pin "1") (pinfunction "1_1") (pintype "unspecified"))
      (node (ref "C15") (pin "1") (pinfunction "1_1") (pintype "input"))
      (node (ref "C17") (pin "1") (pinfunction "1_1") (pintype "unspecified"))
      (node (ref "C20") (pin "1") (pinfunction "1_1") (pintype "unspecified"))
      (node (ref "C21") (pin "1") (pinfunction "1_1") (pintype "input"))
      (node (ref "C22") (pin "1") (pinfunction "1_1") (pintype "input"))
      (node (ref "C23") (pin "1") (pinfunction "1_1") (pintype "input"))
      (node (ref "C24") (pin "1") (pinfunction "1_1") (pintype "input"))
      (node (ref "C25") (pin "2") (pinfunction "2_2") (pintype "input"))
      (node (ref "C27") (pin "1") (pinfunction "1_1") (pintype "input"))
      (node (ref "C28") (pin "1") (pinfunction "1_1") (pintype "input"))
      (node (ref "C3") (pin "1") (pinfunction "1_1") (pintype "input"))
      (node (ref "C32") (pin "2") (pinfunction "2_2") (pintype "input"))
      (node (ref "C35") (pin "1") (pinfunction "1_1") (pintype "input"))
      (node (ref "C36") (pin "1") (pinfunction "1_1") (pintype "input"))
      (node (ref "C38") (pin "2") (pinfunction "2_2") (pintype "input"))
      (node (ref "C39") (pin "2") (pinfunction "2_2") (pintype "input"))
      (node (ref "C40") (pin "1") (pinfunction "1_1") (pintype "input"))
      (node (ref "C41") (pin "1") (pinfunction "1_1") (pintype "input"))
      (node (ref "C42") (pin "1") (pinfunction "1_1") (pintype "input"))
      (node (ref "C43") (pin "1") (pinfunction "1_1") (pintype "input"))
      (node (ref "C44") (pin "1") (pinfunction "1_1") (pintype "input"))
      (node (ref "C45") (pin "1") (pinfunction "1_1") (pintype "input"))
      (node (ref "C47") (pin "1") (pinfunction "1_1") (pintype "input"))
      (node (ref "C48") (pin "1") (pinfunction "1_1") (pintype "input"))
      (node (ref "C49") (pin "1") (pinfunction "1_1") (pintype "input"))
      (node (ref "C50") (pin "1") (pinfunction "1_1") (pintype "input"))
      (node (ref "C52") (pin "1") (pinfunction "1_1") (pintype "input"))
      (node (ref "C53") (pin "1") (pinfunction "1_1") (pintype "input"))
      (node (ref "C6") (pin "1") (pinfunction "1_1") (pintype "input"))
      (node (ref "C62") (pin "1") (pinfunction "1_1") (pintype "input"))
      (node (ref "C63") (pin "1") (pinfunction "1_1") (pintype "input"))
      (node (ref "C64") (pin "1") (pinfunction "1_1") (pintype "input"))
      (node (ref "C65") (pin "1") (pinfunction "1_1") (pintype "input"))
      (node (ref "C66") (pin "1") (pinfunction "1_1") (pintype "input"))
      (node (ref "C7") (pin "1") (pinfunction "1_1") (pintype "unspecified"))
      (node (ref "C76") (pin "2") (pinfunction "2_2") (pintype "input"))
      (node (ref "C77") (pin "1") (pinfunction "1_1") (pintype "input"))
      (node (ref "C78") (pin "1") (pinfunction "1_1") (pintype "input"))
      (node (ref "C8") (pin "1") (pinfunction "1_1") (pintype "input"))
      (node (ref "C80") (pin "1") (pinfunction "1_1") (pintype "input"))
      (node (ref "C81") (pin "2") (pinfunction "2_2") (pintype "input"))
      (node (ref "CN2") (pin "1") (pinfunction "1_1") (pintype "unspecified"))
      (node (ref "D10") (pin "2") (pinfunction "A_2") (pintype "unspecified"))
      (node (ref "D2") (pin "2") (pinfunction "A_2") (pintype "unspecified"))
      (node (ref "D3") (pin "1") (pinfunction "K_1") (pintype "unspecified"))
      (node (ref "D7") (pin "1") (pinfunction "1_1") (pintype "unspecified"))
      (node (ref "D9") (pin "1") (pinfunction "K_1") (pintype "unspecified"))
      (node (ref "FPC1") (pin "1") (pinfunction "1_1") (pintype "unspecified"))
      (node (ref "FPC1") (pin "11") (pinfunction "11_11") (pintype "unspecified"))
      (node (ref "FPC1") (pin "12") (pinfunction "12_12") (pintype "unspecified"))
      (node (ref "L3") (pin "3") (pinfunction "3_3") (pintype "unspecified"))
      (node (ref "LED1") (pin "1") (pinfunction "C_1") (pintype "input"))
      (node (ref "LED2") (pin "1") (pinfunction "C_1") (pintype "input"))
      (node (ref "LED3") (pin "1") (pinfunction "C_1") (pintype "input"))
      (node (ref "Q4") (pin "2") (pinfunction "E_2") (pintype "input"))
      (node (ref "Q7") (pin "2") (pinfunction "E_2") (pintype "input"))
      (node (ref "Q8") (pin "2") (pinfunction "S_2") (pintype "unspecified"))
      (node (ref "Q9") (pin "2") (pinfunction "E_2") (pintype "input"))
      (node (ref "R10") (pin "1") (pinfunction "1_1") (pintype "input"))
      (node (ref "R11") (pin "1") (pinfunction "1_1") (pintype "input"))
      (node (ref "R14") (pin "1") (pinfunction "1_1") (pintype "input"))
      (node (ref "R19") (pin "2") (pinfunction "2_2") (pintype "input"))
      (node (ref "R2") (pin "1") (pinfunction "1_1") (pintype "input"))
      (node (ref "R24") (pin "1") (pinfunction "1_1") (pintype "unspecified"))
      (node (ref "R25") (pin "1") (pinfunction "1_1") (pintype "unspecified"))
      (node (ref "R26") (pin "1") (pinfunction "1_1") (pintype "unspecified"))
      (node (ref "R31") (pin "2") (pinfunction "2_2") (pintype "input"))
      (node (ref "R33") (pin "1") (pinfunction "1_1") (pintype "input"))
      (node (ref "R34") (pin "1") (pinfunction "1_1") (pintype "input"))
      (node (ref "R35") (pin "1") (pinfunction "1_1") (pintype "input"))
      (node (ref "R49") (pin "1") (pinfunction "1_1") (pintype "input"))
      (node (ref "R5") (pin "1") (pinfunction "1_1") (pintype "input"))
      (node (ref "R54") (pin "1") (pinfunction "1_1") (pintype "input"))
      (node (ref "R58") (pin "1") (pinfunction "1_1") (pintype "input"))
      (node (ref "R78") (pin "2") (pinfunction "2_2") (pintype "input"))
      (node (ref "R8") (pin "1") (pinfunction "1_1") (pintype "input"))
      (node (ref "SCREW2") (pin "1") (pinfunction "1_1") (pintype "input"))
      (node (ref "SCREW3") (pin "1") (pinfunction "1_1") (pintype "input"))
      (node (ref "SW1") (pin "6") (pinfunction "6_6") (pintype "unspecified"))
      (node (ref "SW1") (pin "7") (pinfunction "7_7") (pintype "unspecified"))
      (node (ref "SW1") (pin "C") (pinfunction "C_C") (pintype "unspecified"))
      (node (ref "SW1") (pin "E") (pinfunction "E_E") (pintype "unspecified"))
      (node (ref "SW2") (pin "1") (pinfunction "1_1") (pintype "unspecified"))
      (node (ref "SW2") (pin "3") (pinfunction "3_3") (pintype "unspecified"))
      (node (ref "SW2") (pin "4") (pinfunction "4_4") (pintype "unspecified"))
      (node (ref "U12") (pin "3") (pinfunction "ANODE_3") (pintype "unspecified"))
      (node (ref "U13") (pin "49") (pinfunction "GND_49") (pintype "unspecified"))
      (node (ref "U14") (pin "1") (pinfunction "GND_1") (pintype "unspecified"))
      (node (ref "U19") (pin "3") (pinfunction "S_3") (pintype "unspecified"))
      (node (ref "U2") (pin "2") (pinfunction "GND_2") (pintype "unspecified"))
      (node (ref "U2") (pin "3") (pinfunction "OFF_3") (pintype "unspecified"))
      (node (ref "U20") (pin "3") (pinfunction "3_3") (pintype "unspecified"))
      (node (ref "U20") (pin "4") (pinfunction "4_4") (pintype "unspecified"))
      (node (ref "U3") (pin "11") (pinfunction "GND_11") (pintype "unspecified"))
      (node (ref "U3") (pin "3") (pinfunction "CFG3_3") (pintype "unspecified"))
      (node (ref "U3") (pin "9") (pinfunction "CFG1_9") (pintype "unspecified"))
      (node (ref "U4") (pin "2") (pinfunction "GND_2") (pintype "unspecified"))
      (node (ref "U5") (pin "2") (pinfunction "GND_2") (pintype "unspecified"))
      (node (ref "U6") (pin "10") (pinfunction "AGND_10") (pintype "unspecified"))
      (node (ref "U6") (pin "22") (pinfunction "PGND_22") (pintype "unspecified"))
      (node (ref "U6") (pin "29") (pinfunction "EP_29") (pintype "unspecified"))
      (node (ref "USB1") (pin "1") (pinfunction "EP_1") (pintype "unspecified"))
      (node (ref "USB1") (pin "2") (pinfunction "EP_2") (pintype "unspecified"))
      (node (ref "USB1") (pin "3") (pinfunction "EP_3") (pintype "unspecified"))
      (node (ref "USB1") (pin "4") (pinfunction "EP_4") (pintype "unspecified"))
      (node (ref "USB1") (pin "A1") (pinfunction "GND_A1") (pintype "unspecified"))
      (node (ref "USB1") (pin "A12") (pinfunction "GND_A12") (pintype "unspecified"))
      (node (ref "USB1") (pin "B1") (pinfunction "GND_B1") (pintype "unspecified"))
      (node (ref "USB1") (pin "B12") (pinfunction "GND_B12") (pintype "unspecified"))
    )
    (net (code "27") (name "HO1") (class "Default")
      (node (ref "R27") (pin "1") (pinfunction "1_1") (pintype "input"))
      (node (ref "U6") (pin "27") (pinfunction "HDRV1_27") (pintype "unspecified"))
    )
    (net (code "28") (name "HO2") (class "Default")
      (node (ref "R29") (pin "2") (pinfunction "2_2") (pintype "input"))
      (node (ref "U6") (pin "19") (pinfunction "HDRV2_19") (pintype "unspecified"))
    )
    (net (code "29") (name "IO0") (class "Default")
      (node (ref "Q6") (pin "3") (pinfunction "C_3") (pintype "unspecified"))
      (node (ref "R31") (pin "1") (pinfunction "1_1") (pintype "input"))
      (node (ref "U13") (pin "23") (pinfunction "IO0_23") (pintype "unspecified"))
      (node (ref "U6") (pin "1") (pinfunction "EN/UVLO_1") (pintype "unspecified"))
    )
    (net (code "30") (name "ISENSE") (class "Default")
      (node (ref "R41") (pin "1") (pinfunction "1_1") (pintype "input"))
      (node (ref "U10") (pin "8") (pinfunction "OUT_8") (pintype "unspecified"))
      (node (ref "U13") (pin "11") (pinfunction "IO35_11") (pintype "unspecified"))
    )
    (net (code "31") (name "ISET") (class "Default")
      (node (ref "R42") (pin "1") (pinfunction "1_1") (pintype "input"))
      (node (ref "R43") (pin "2") (pinfunction "2_2") (pintype "input"))
      (node (ref "U16") (pin "2") (pinfunction "VOUTB_2") (pintype "output"))
    )
    (net (code "32") (name "IS_N") (class "Default")
      (node (ref "C54") (pin "1") (pinfunction "1_1") (pintype "input"))
      (node (ref "R40") (pin "2") (pinfunction "2_2") (pintype "input"))
      (node (ref "U10") (pin "3") (pinfunction "IN-_3") (pintype "unspecified"))
    )
    (net (code "33") (name "IS_P") (class "Default")
      (node (ref "C54") (pin "2") (pinfunction "2_2") (pintype "input"))
      (node (ref "R39") (pin "2") (pinfunction "2_2") (pintype "input"))
      (node (ref "U10") (pin "2") (pinfunction "IN+_2") (pintype "unspecified"))
    )
    (net (code "34") (name "LCD_CS") (class "Default")
      (node (ref "FPC1") (pin "5") (pinfunction "5_5") (pintype "unspecified"))
      (node (ref "U13") (pin "14") (pinfunction "IO25_14") (pintype "unspecified"))
    )
    (net (code "35") (name "LCD_LED") (class "Default")
      (node (ref "R74") (pin "1") (pinfunction "1_1") (pintype "input"))
      (node (ref "U13") (pin "17") (pinfunction "IO14_17") (pintype "unspecified"))
    )
    (net (code "36") (name "LED_G") (class "Default")
      (node (ref "R77") (pin "2") (pinfunction "2_2") (pintype "input"))
      (node (ref "U13") (pin "29") (pinfunction "SD3_29") (pintype "unspecified"))
      (node (ref "U20") (pin "1") (pinfunction "1_1") (pintype "unspecified"))
    )
    (net (code "37") (name "LED_R") (class "Default")
      (node (ref "R76") (pin "2") (pinfunction "2_2") (pintype "input"))
      (node (ref "U13") (pin "28") (pinfunction "SD2_28") (pintype "unspecified"))
      (node (ref "U20") (pin "2") (pinfunction "2_2") (pintype "unspecified"))
    )
    (net (code "38") (name "LO1") (class "Default")
      (node (ref "R28") (pin "1") (pinfunction "1_1") (pintype "input"))
      (node (ref "U6") (pin "25") (pinfunction "LDRV1_25") (pintype "unspecified"))
    )
    (net (code "39") (name "LO2") (class "Default")
      (node (ref "R30") (pin "2") (pinfunction "2_2") (pintype "input"))
      (node (ref "U6") (pin "21") (pinfunction "LDRV2_21") (pintype "unspecified"))
    )
    (net (code "40") (name "MOSI") (class "Default")
      (node (ref "FPC1") (pin "6") (pinfunction "6_6") (pintype "unspecified"))
      (node (ref "U13") (pin "36") (pinfunction "IO23_36") (pintype "unspecified"))
      (node (ref "U16") (pin "8") (pinfunction "DIN_8") (pintype "unspecified"))
    )
    (net (code "41") (name "Net-(C28-Pad2)") (class "Default")
      (node (ref "C28") (pin "2") (pinfunction "2_2") (pintype "input"))
      (node (ref "R17") (pin "1") (pinfunction "1_1") (pintype "input"))
    )
    (net (code "42") (name "Net-(C33-Pad1)") (class "Default")
      (node (ref "C33") (pin "1") (pinfunction "1_1") (pintype "input"))
      (node (ref "R33") (pin "2") (pinfunction "2_2") (pintype "input"))
    )
    (net (code "43") (name "Net-(C34-Pad1)") (class "Default")
      (node (ref "C34") (pin "1") (pinfunction "1_1") (pintype "input"))
      (node (ref "R34") (pin "2") (pinfunction "2_2") (pintype "input"))
    )
    (net (code "44") (name "Net-(C57-Pad2)") (class "Default")
      (node (ref "C57") (pin "2") (pinfunction "2_2") (pintype "input"))
      (node (ref "R44") (pin "1") (pinfunction "1_1") (pintype "input"))
    )
    (net (code "45") (name "Net-(CN1--)") (class "Default")
      (node (ref "C37") (pin "1") (pinfunction "1_1") (pintype "input"))
      (node (ref "CN1") (pin "1") (pinfunction "-_1") (pintype "unspecified"))
      (node (ref "D1") (pin "1") (pinfunction "K_1") (pintype "input"))
      (node (ref "P1") (pin "3") (pinfunction "3_3") (pintype "unspecified"))
      (node (ref "P1") (pin "4") (pinfunction "4_4") (pintype "unspecified"))
      (node (ref "U19") (pin "2") (pinfunction "D_2") (pintype "unspecified"))
    )
    (net (code "46") (name "Net-(CN2-Pad2)") (class "Default")
      (node (ref "CN2") (pin "2") (pinfunction "2_2") (pintype "unspecified"))
      (node (ref "R51") (pin "1") (pinfunction "1_1") (pintype "input"))
    )
    (net (code "47") (name "Net-(CN2-Pad3)") (class "Default")
      (node (ref "CN2") (pin "3") (pinfunction "3_3") (pintype "unspecified"))
      (node (ref "R52") (pin "1") (pinfunction "1_1") (pintype "input"))
    )
    (net (code "48") (name "Net-(D2-K)") (class "Default")
      (node (ref "D2") (pin "1") (pinfunction "K_1") (pintype "unspecified"))
      (node (ref "R1") (pin "1") (pinfunction "1_1") (pintype "input"))
      (node (ref "R2") (pin "2") (pinfunction "2_2") (pintype "input"))
      (node (ref "U19") (pin "1") (pinfunction "G_1") (pintype "unspecified"))
    )
    (net (code "49") (name "Net-(D10-K)") (class "Default")
      (node (ref "D10") (pin "1") (pinfunction "K_1") (pintype "unspecified"))
      (node (ref "D22") (pin "2") (pinfunction "2_2") (pintype "unspecified"))
      (node (ref "D9") (pin "2") (pinfunction "A_2") (pintype "unspecified"))
      (node (ref "R45") (pin "1") (pinfunction "1_1") (pintype "input"))
      (node (ref "R49") (pin "2") (pinfunction "2_2") (pintype "input"))
      (node (ref "R51") (pin "2") (pinfunction "2_2") (pintype "input"))
    )
    (net (code "50") (name "Net-(D11-A)") (class "Default")
      (node (ref "D11") (pin "2") (pinfunction "A_2") (pintype "unspecified"))
      (node (ref "D12") (pin "1") (pinfunction "K_1") (pintype "unspecified"))
      (node (ref "D22") (pin "1") (pinfunction "1_1") (pintype "unspecified"))
      (node (ref "R46") (pin "1") (pinfunction "1_1") (pintype "input"))
      (node (ref "R50") (pin "1") (pinfunction "1_1") (pintype "input"))
      (node (ref "R52") (pin "2") (pinfunction "2_2") (pintype "input"))
    )
    (net (code "51") (name "Net-(D13-C)") (class "Default")
      (node (ref "D13") (pin "1") (pinfunction "C_1") (pintype "unspecified"))
      (node (ref "D14") (pin "2") (pinfunction "A_2") (pintype "unspecified"))
    )
    (net (code "52") (name "Net-(D14-C)") (class "Default")
      (node (ref "C61") (pin "1") (pinfunction "1_1") (pintype "input"))
      (node (ref "D14") (pin "1") (pinfunction "C_1") (pintype "unspecified"))
      (node (ref "Q5") (pin "1") (pinfunction "B_1") (pintype "unspecified"))
      (node (ref "R59") (pin "2") (pinfunction "2_2") (pintype "input"))
    )
    (net (code "53") (name "Net-(D15-A)") (class "Default")
      (node (ref "C70") (pin "2") (pinfunction "2_2") (pintype "input"))
      (node (ref "D15") (pin "2") (pinfunction "A_2") (pintype "unspecified"))
      (node (ref "D16") (pin "1") (pinfunction "C_1") (pintype "unspecified"))
    )
    (net (code "54") (name "Net-(D17-A)") (class "Default")
      (node (ref "C72") (pin "2") (pinfunction "2_2") (pintype "input"))
      (node (ref "D17") (pin "2") (pinfunction "A_2") (pintype "unspecified"))
      (node (ref "D18") (pin "1") (pinfunction "C_1") (pintype "unspecified"))
    )
    (net (code "55") (name "Net-(D19-A)") (class "Default")
      (node (ref "BUZZER1") (pin "2") (pinfunction "2_2") (pintype "unspecified"))
      (node (ref "D19") (pin "2") (pinfunction "A_2") (pintype "unspecified"))
      (node (ref "Q7") (pin "3") (pinfunction "C_3") (pintype "input"))
    )
    (net (code "56") (name "Net-(D20-A)") (class "Default")
      (node (ref "CN3") (pin "2") (pinfunction "2_2") (pintype "unspecified"))
      (node (ref "D20") (pin "2") (pinfunction "A_2") (pintype "unspecified"))
      (node (ref "Q8") (pin "3") (pinfunction "D_3") (pintype "unspecified"))
    )
    (net (code "57") (name "Net-(D25-K)") (class "Default")
      (node (ref "D25") (pin "1") (pinfunction "K_1") (pintype "unspecified"))
      (node (ref "R9") (pin "1") (pinfunction "1_1") (pintype "input"))
    )
    (net (code "58") (name "Net-(LED2-A)") (class "Default")
      (node (ref "LED2") (pin "2") (pinfunction "A_2") (pintype "input"))
      (node (ref "R76") (pin "1") (pinfunction "1_1") (pintype "input"))
    )
    (net (code "59") (name "Net-(LED3-A)") (class "Default")
      (node (ref "LED3") (pin "2") (pinfunction "A_2") (pintype "input"))
      (node (ref "R77") (pin "1") (pinfunction "1_1") (pintype "input"))
    )
    (net (code "60") (name "Net-(Q3-B)") (class "Default")
      (node (ref "Q3") (pin "1") (pinfunction "B_1") (pintype "input"))
      (node (ref "R55") (pin "2") (pinfunction "2_2") (pintype "input"))
      (node (ref "R56") (pin "2") (pinfunction "2_2") (pintype "input"))
    )
    (net (code "61") (name "Net-(Q3-C)") (class "Default")
      (node (ref "Q3") (pin "3") (pinfunction "C_3") (pintype "input"))
      (node (ref "R57") (pin "2") (pinfunction "2_2") (pintype "input"))
    )
    (net (code "62") (name "Net-(Q4-B)") (class "Default")
      (node (ref "Q4") (pin "1") (pinfunction "B_1") (pintype "input"))
      (node (ref "R57") (pin "1") (pinfunction "1_1") (pintype "input"))
      (node (ref "R58") (pin "2") (pinfunction "2_2") (pintype "input"))
    )
    (net (code "63") (name "Net-(Q6-B-Pad2)") (class "Default")
      (node (ref "Q6") (pin "2") (pinfunction "B_2") (pintype "unspecified"))
      (node (ref "R62") (pin "1") (pinfunction "1_1") (pintype "input"))
    )
    (net (code "64") (name "Net-(Q6-B-Pad5)") (class "Default")
      (node (ref "Q6") (pin "5") (pinfunction "B_5") (pintype "unspecified"))
      (node (ref "R63") (pin "2") (pinfunction "2_2") (pintype "input"))
    )
    (net (code "65") (name "Net-(Q7-B)") (class "Default")
      (node (ref "Q7") (pin "1") (pinfunction "B_1") (pintype "input"))
      (node (ref "R70") (pin "2") (pinfunction "2_2") (pintype "input"))
    )
    (net (code "66") (name "Net-(Q8-G)") (class "Default")
      (node (ref "Q8") (pin "1") (pinfunction "G_1") (pintype "unspecified"))
      (node (ref "R71") (pin "2") (pinfunction "2_2") (pintype "input"))
    )
    (net (code "67") (name "Net-(Q9-B)") (class "Default")
      (node (ref "Q9") (pin "1") (pinfunction "B_1") (pintype "input"))
      (node (ref "R74") (pin "2") (pinfunction "2_2") (pintype "input"))
    )
    (net (code "68") (name "Net-(Q9-C)") (class "Default")
      (node (ref "FPC1") (pin "10") (pinfunction "10_10") (pintype "unspecified"))
      (node (ref "Q9") (pin "3") (pinfunction "C_3") (pintype "input"))
    )
    (net (code "69") (name "Net-(U1-G)") (class "Default")
      (node (ref "R23") (pin "2") (pinfunction "2_2") (pintype "input"))
      (node (ref "R30") (pin "1") (pinfunction "1_1") (pintype "input"))
      (node (ref "U1") (pin "1") (pinfunction "G_1") (pintype "unspecified"))
    )
    (net (code "70") (name "Net-(U3-CFG2)") (class "Default")
      (node (ref "C8") (pin "2") (pinfunction "2_2") (pintype "input"))
      (node (ref "R4") (pin "1") (pinfunction "1_1") (pintype "input"))
      (node (ref "U3") (pin "1") (pinfunction "VDD_1") (pintype "unspecified"))
      (node (ref "U3") (pin "2") (pinfunction "CFG2_2") (pintype "unspecified"))
    )
    (net (code "71") (name "Net-(U3-DM)") (class "Default")
      (node (ref "U3") (pin "4") (pinfunction "DP_4") (pintype "unspecified"))
      (node (ref "U3") (pin "5") (pinfunction "DM_5") (pintype "unspecified"))
    )
    (net (code "72") (name "Net-(U3-VBUS)") (class "Default")
      (node (ref "R3") (pin "2") (pinfunction "2_2") (pintype "input"))
      (node (ref "U3") (pin "8") (pinfunction "VBUS_8") (pintype "unspecified"))
    )
    (net (code "73") (name "Net-(U4-BOOT)") (class "Default")
      (node (ref "C12") (pin "1") (pinfunction "1_1") (pintype "input"))
      (node (ref "U4") (pin "1") (pinfunction "BOOT_1") (pintype "unspecified"))
    )
    (net (code "74") (name "Net-(U4-FB)") (class "Default")
      (node (ref "C13") (pin "1") (pinfunction "1_1") (pintype "input"))
      (node (ref "R5") (pin "2") (pinfunction "2_2") (pintype "input"))
      (node (ref "R6") (pin "1") (pinfunction "1_1") (pintype "input"))
      (node (ref "U4") (pin "3") (pinfunction "FB_3") (pintype "unspecified"))
    )
    (net (code "75") (name "Net-(U4-LX)") (class "Default")
      (node (ref "C12") (pin "2") (pinfunction "2_2") (pintype "input"))
      (node (ref "L1") (pin "1") (pinfunction "1_1") (pintype "unspecified"))
      (node (ref "U4") (pin "6") (pinfunction "LX_6") (pintype "unspecified"))
    )
    (net (code "76") (name "Net-(U5-BS)") (class "Default")
      (node (ref "C16") (pin "1") (pinfunction "1_1") (pintype "input"))
      (node (ref "U5") (pin "1") (pinfunction "BS_1") (pintype "unspecified"))
    )
    (net (code "77") (name "Net-(U5-FB)") (class "Default")
      (node (ref "C19") (pin "1") (pinfunction "1_1") (pintype "input"))
      (node (ref "R7") (pin "1") (pinfunction "1_1") (pintype "input"))
      (node (ref "R8") (pin "2") (pinfunction "2_2") (pintype "input"))
      (node (ref "U5") (pin "3") (pinfunction "FB_3") (pintype "unspecified"))
    )
    (net (code "78") (name "Net-(U5-LX)") (class "Default")
      (node (ref "C16") (pin "2") (pinfunction "2_2") (pintype "input"))
      (node (ref "L2") (pin "1") (pinfunction "1_1") (pintype "unspecified"))
      (node (ref "U5") (pin "6") (pinfunction "LX_6") (pintype "unspecified"))
    )
    (net (code "79") (name "Net-(U6-DITH)") (class "Default")
      (node (ref "C22") (pin "2") (pinfunction "2_2") (pintype "input"))
      (node (ref "U6") (pin "5") (pinfunction "DITH_5") (pintype "unspecified"))
    )
    (net (code "80") (name "Net-(U6-FB)") (class "Default")
      (node (ref "R12") (pin "1") (pinfunction "1_1") (pintype "input"))
      (node (ref "R13") (pin "2") (pinfunction "2_2") (pintype "input"))
      (node (ref "R14") (pin "2") (pinfunction "2_2") (pintype "input"))
      (node (ref "U6") (pin "11") (pinfunction "FB_11") (pintype "unspecified"))
    )
    (net (code "81") (name "Net-(U6-ISNS(+))") (class "Default")
      (node (ref "C26") (pin "2") (pinfunction "2_2") (pintype "input"))
      (node (ref "R16") (pin "2") (pinfunction "2_2") (pintype "input"))
      (node (ref "U6") (pin "14") (pinfunction "ISNS(+)_14") (pintype "unspecified"))
    )
    (net (code "82") (name "Net-(U6-ISNS(-))") (class "Default")
      (node (ref "C26") (pin "1") (pinfunction "1_1") (pintype "input"))
      (node (ref "R15") (pin "2") (pinfunction "2_2") (pintype "input"))
      (node (ref "U6") (pin "13") (pinfunction "ISNS(-)_13") (pintype "unspecified"))
    )
    (net (code "83") (name "Net-(U6-MODE)") (class "Default")
      (node (ref "R11") (pin "2") (pinfunction "2_2") (pintype "input"))
      (node (ref "U6") (pin "4") (pinfunction "MODE_4") (pintype "unspecified"))
    )
    (net (code "84") (name "Net-(U6-RT)") (class "Default")
      (node (ref "R10") (pin "2") (pinfunction "2_2") (pintype "input"))
      (node (ref "U6") (pin "6") (pinfunction "RT_6") (pintype "unspecified"))
    )
    (net (code "85") (name "Net-(U6-SLOPE)") (class "Default")
      (node (ref "C23") (pin "2") (pinfunction "2_2") (pintype "input"))
      (node (ref "U6") (pin "7") (pinfunction "SLOPE_7") (pintype "unspecified"))
    )
    (net (code "86") (name "Net-(U6-SS)") (class "Default")
      (node (ref "C24") (pin "2") (pinfunction "2_2") (pintype "input"))
      (node (ref "U6") (pin "8") (pinfunction "SS_8") (pintype "unspecified"))
    )
    (net (code "87") (name "Net-(U6-VIN)") (class "Default")
      (node (ref "C25") (pin "1") (pinfunction "1_1") (pintype "input"))
      (node (ref "R9") (pin "2") (pinfunction "2_2") (pintype "input"))
      (node (ref "U6") (pin "2") (pinfunction "VIN_2") (pintype "unspecified"))
    )
    (net (code "88") (name "Net-(U7-G)") (class "Default")
      (node (ref "R20") (pin "2") (pinfunction "2_2") (pintype "input"))
      (node (ref "R27") (pin "2") (pinfunction "2_2") (pintype "input"))
      (node (ref "U7") (pin "1") (pinfunction "G_1") (pintype "unspecified"))
    )
    (net (code "89") (name "Net-(U8-G)") (class "Default")
      (node (ref "R21") (pin "2") (pinfunction "2_2") (pintype "input"))
      (node (ref "R28") (pin "2") (pinfunction "2_2") (pintype "input"))
      (node (ref "U8") (pin "1") (pinfunction "G_1") (pintype "unspecified"))
    )
    (net (code "90") (name "Net-(U9-G)") (class "Default")
      (node (ref "R22") (pin "2") (pinfunction "2_2") (pintype "input"))
      (node (ref "R29") (pin "1") (pinfunction "1_1") (pintype "input"))
      (node (ref "U9") (pin "1") (pinfunction "G_1") (pintype "unspecified"))
    )
    (net (code "91") (name "Net-(U11A-+IN_2)") (class "Default")
      (node (ref "C56") (pin "2") (pinfunction "2_2") (pintype "input"))
      (node (ref "R42") (pin "2") (pinfunction "2_2") (pintype "input"))
      (node (ref "U11") (pin "5") (pinfunction "+IN_2_5") (pintype "unspecified"))
    )
    (net (code "92") (name "Net-(U11A--IN_2)") (class "Default")
      (node (ref "C57") (pin "1") (pinfunction "1_1") (pintype "input"))
      (node (ref "C58") (pin "1") (pinfunction "1_1") (pintype "input"))
      (node (ref "R41") (pin "2") (pinfunction "2_2") (pintype "input"))
      (node (ref "U11") (pin "6") (pinfunction "-IN_2_6") (pintype "unspecified"))
    )
    (net (code "93") (name "Net-(U11B-+IN_1)") (class "Default")
      (node (ref "R46") (pin "2") (pinfunction "2_2") (pintype "input"))
      (node (ref "R48") (pin "1") (pinfunction "1_1") (pintype "input"))
      (node (ref "U11") (pin "3") (pinfunction "+IN_1_3") (pintype "unspecified"))
    )
    (net (code "94") (name "Net-(U11B--IN_1)") (class "Default")
      (node (ref "R45") (pin "2") (pinfunction "2_2") (pintype "input"))
      (node (ref "R47") (pin "1") (pinfunction "1_1") (pintype "input"))
      (node (ref "U11") (pin "2") (pinfunction "-IN_1_2") (pintype "unspecified"))
    )
    (net (code "95") (name "Net-(U12-CATHODE)") (class "Default")
      (node (ref "R55") (pin "1") (pinfunction "1_1") (pintype "input"))
      (node (ref "U12") (pin "1") (pinfunction "CATHODE_1") (pintype "unspecified"))
    )
    (net (code "96") (name "Net-(U12-REF)") (class "Default")
      (node (ref "R53") (pin "1") (pinfunction "1_1") (pintype "input"))
      (node (ref "R54") (pin "2") (pinfunction "2_2") (pintype "input"))
      (node (ref "U12") (pin "2") (pinfunction "REF_2") (pintype "unspecified"))
    )
    (net (code "97") (name "Net-(U13-LNA_IN)") (class "Default")
      (node (ref "L5") (pin "2") (pinfunction "2_2") (pintype "unspecified"))
      (node (ref "U13") (pin "2") (pinfunction "LNA_IN_2") (pintype "unspecified"))
    )
    (net (code "98") (name "Net-(U16-VREFIN{slash}VREFOUT)") (class "Default")
      (node (ref "C74") (pin "2") (pinfunction "2_2") (pintype "input"))
      (node (ref "R66") (pin "1") (pinfunction "1_1") (pintype "input"))
      (node (ref "U16") (pin "10") (pinfunction "VREFIN/VREFOUT_10") (pintype "bidirectional"))
    )
    (net (code "99") (name "Net-(U18-G)") (class "Default")
      (node (ref "U18") (pin "1") (pinfunction "G_1") (pintype "unspecified"))
      (node (ref "U2") (pin "5") (pinfunction "GATE_5") (pintype "unspecified"))
    )
    (net (code "100") (name "PCNT_A") (class "Default")
      (node (ref "C76") (pin "1") (pinfunction "1_1") (pintype "input"))
      (node (ref "R68") (pin "2") (pinfunction "2_2") (pintype "input"))
      (node (ref "SW1") (pin "A") (pinfunction "A_A") (pintype "unspecified"))
      (node (ref "U13") (pin "39") (pinfunction "IO22_39") (pintype "unspecified"))
    )
    (net (code "101") (name "PCNT_B") (class "Default")
      (node (ref "C77") (pin "2") (pinfunction "2_2") (pintype "input"))
      (node (ref "R69") (pin "1") (pinfunction "1_1") (pintype "input"))
      (node (ref "SW1") (pin "B") (pinfunction "B_B") (pintype "unspecified"))
      (node (ref "U13") (pin "42") (pinfunction "IO21_42") (pintype "unspecified"))
    )
    (net (code "102") (name "PG") (class "Default")
      (node (ref "LED1") (pin "2") (pinfunction "A_2") (pintype "input"))
      (node (ref "R32") (pin "1") (pinfunction "1_1") (pintype "input"))
      (node (ref "U6") (pin "17") (pinfunction "PGOOD_17") (pintype "unspecified"))
    )
    (net (code "103") (name "PWMA") (class "Default")
      (node (ref "C70") (pin "1") (pinfunction "1_1") (pintype "input"))
      (node (ref "U13") (pin "13") (pinfunction "IO33_13") (pintype "unspecified"))
    )
    (net (code "104") (name "PWMB") (class "Default")
      (node (ref "C72") (pin "1") (pinfunction "1_1") (pintype "input"))
      (node (ref "U13") (pin "12") (pinfunction "IO32_12") (pintype "unspecified"))
    )
    (net (code "105") (name "PWR_IN") (class "Default")
      (node (ref "C67") (pin "2") (pinfunction "2_2") (pintype "input"))
      (node (ref "R64") (pin "1") (pinfunction "1_1") (pintype "input"))
      (node (ref "R65") (pin "1") (pinfunction "1_1") (pintype "input"))
      (node (ref "U13") (pin "10") (pinfunction "IO34_10") (pintype "unspecified"))
    )
    (net (code "106") (name "RTS") (class "Default")
      (node (ref "Q6") (pin "1") (pinfunction "E_1") (pintype "unspecified"))
      (node (ref "R63") (pin "1") (pinfunction "1_1") (pintype "input"))
      (node (ref "U14") (pin "14") (pinfunction "RTS#_14") (pintype "unspecified"))
    )
    (net (code "107") (name "RXD") (class "Default")
      (node (ref "U13") (pin "41") (pinfunction "U0TXD_41") (pintype "unspecified"))
      (node (ref "U14") (pin "3") (pinfunction "RXD_3") (pintype "unspecified"))
    )
    (net (code "108") (name "SCLK") (class "Default")
      (node (ref "FPC1") (pin "3") (pinfunction "3_3") (pintype "unspecified"))
      (node (ref "U13") (pin "35") (pinfunction "IO18_35") (pintype "unspecified"))
      (node (ref "U16") (pin "7") (pinfunction "SCLK_7") (pintype "unspecified"))
    )
    (net (code "109") (name "SW1") (class "Default")
      (node (ref "C30") (pin "1") (pinfunction "1_1") (pintype "input"))
      (node (ref "C33") (pin "2") (pinfunction "2_2") (pintype "input"))
      (node (ref "D5") (pin "1") (pinfunction "K_1") (pintype "unspecified"))
      (node (ref "L3") (pin "1") (pinfunction "1_1") (pintype "unspecified"))
      (node (ref "R20") (pin "1") (pinfunction "1_1") (pintype "input"))
      (node (ref "U6") (pin "28") (pinfunction "SW1_28") (pintype "unspecified"))
      (node (ref "U7") (pin "3") (pinfunction "S_3") (pintype "unspecified"))
      (node (ref "U8") (pin "2") (pinfunction "D_2") (pintype "unspecified"))
    )
    (net (code "110") (name "SW2") (class "Default")
      (node (ref "C31") (pin "1") (pinfunction "1_1") (pintype "input"))
      (node (ref "C34") (pin "2") (pinfunction "2_2") (pintype "input"))
      (node (ref "D26") (pin "2") (pinfunction "A_2") (pintype "unspecified"))
      (node (ref "L3") (pin "2") (pinfunction "2_2") (pintype "unspecified"))
      (node (ref "R22") (pin "1") (pinfunction "1_1") (pintype "input"))
      (node (ref "U1") (pin "2") (pinfunction "D_2") (pintype "unspecified"))
      (node (ref "U6") (pin "18") (pinfunction "SW2_18") (pintype "unspecified"))
      (node (ref "U9") (pin "3") (pinfunction "S_3") (pintype "unspecified"))
    )
    (net (code "111") (name "TEMP") (class "Default")
      (node (ref "C79") (pin "2") (pinfunction "2_2") (pintype "input"))
      (node (ref "R72") (pin "2") (pinfunction "2_2") (pintype "input"))
      (node (ref "R73") (pin "1") (pinfunction "1_1") (pintype "input"))
      (node (ref "U13") (pin "5") (pinfunction "SENSOR_VP_5") (pintype "unspecified"))
    )
    (net (code "112") (name "TXD") (class "Default")
      (node (ref "U13") (pin "40") (pinfunction "U0RXD_40") (pintype "unspecified"))
      (node (ref "U14") (pin "2") (pinfunction "TXD_2") (pintype "unspecified"))
    )
    (net (code "113") (name "USB_N") (class "Default")
      (node (ref "U14") (pin "6") (pinfunction "D-_6") (pintype "unspecified"))
      (node (ref "USB1") (pin "A7") (pinfunction "DN1_A7") (pintype "unspecified"))
      (node (ref "USB1") (pin "B7") (pinfunction "DN2_B7") (pintype "unspecified"))
    )
    (net (code "114") (name "USB_P") (class "Default")
      (node (ref "U14") (pin "5") (pinfunction "D+_5") (pintype "unspecified"))
      (node (ref "USB1") (pin "A6") (pinfunction "DP1_A6") (pintype "unspecified"))
      (node (ref "USB1") (pin "B6") (pinfunction "DP2_B6") (pintype "unspecified"))
    )
    (net (code "115") (name "USET") (class "Default")
      (node (ref "R13") (pin "1") (pinfunction "1_1") (pintype "input"))
      (node (ref "U16") (pin "1") (pinfunction "VOUTA_1") (pintype "output"))
    )
    (net (code "116") (name "VBUS") (class "Default")
      (node (ref "C6") (pin "2") (pinfunction "2_2") (pintype "input"))
      (node (ref "D3") (pin "2") (pinfunction "A_2") (pintype "unspecified"))
      (node (ref "R3") (pin "1") (pinfunction "1_1") (pintype "input"))
      (node (ref "R4") (pin "2") (pinfunction "2_2") (pintype "input"))
      (node (ref "U18") (pin "3") (pinfunction "S_3") (pintype "unspecified"))
      (node (ref "U2") (pin "4") (pinfunction "IN_4") (pintype "unspecified"))
      (node (ref "USB1") (pin "A4") (pinfunction "VBUS_A4") (pintype "unspecified"))
      (node (ref "USB1") (pin "A9") (pinfunction "VBUS_A9") (pintype "unspecified"))
      (node (ref "USB1") (pin "B4") (pinfunction "VBUS_B4") (pintype "unspecified"))
      (node (ref "USB1") (pin "B9") (pinfunction "VBUS_B9") (pintype "unspecified"))
    )
    (net (code "117") (name "VCC") (class "Default")
      (node (ref "C32") (pin "1") (pinfunction "1_1") (pintype "input"))
      (node (ref "D23") (pin "2") (pinfunction "A_2") (pintype "unspecified"))
      (node (ref "D24") (pin "2") (pinfunction "A_2") (pintype "unspecified"))
      (node (ref "R32") (pin "2") (pinfunction "2_2") (pintype "input"))
      (node (ref "U6") (pin "23") (pinfunction "VCC_23") (pintype "unspecified"))
    )
    (net (code "118") (name "VIN") (class "Default")
      (node (ref "C1") (pin "2") (pinfunction "2_2") (pintype "input"))
      (node (ref "C10") (pin "2") (pinfunction "2_2") (pintype "input"))
      (node (ref "C11") (pin "2") (pinfunction "2_2") (pintype "input"))
      (node (ref "C3") (pin "2") (pinfunction "2_2") (pintype "input"))
      (node (ref "C36") (pin "2") (pinfunction "2_2") (pintype "input"))
      (node (ref "C37") (pin "2") (pinfunction "2_2") (pintype "input"))
      (node (ref "C7") (pin "2") (pinfunction "2_2") (pintype "unspecified"))
      (node (ref "C81") (pin "1") (pinfunction "1_1") (pintype "input"))
      (node (ref "CN1") (pin "2") (pinfunction "+_2") (pintype "unspecified"))
      (node (ref "D1") (pin "2") (pinfunction "A_2") (pintype "input"))
      (node (ref "D25") (pin "2") (pinfunction "A_2") (pintype "unspecified"))
      (node (ref "P1") (pin "2") (pinfunction "2_2") (pintype "unspecified"))
      (node (ref "R1") (pin "2") (pinfunction "2_2") (pintype "input"))
      (node (ref "R64") (pin "2") (pinfunction "2_2") (pintype "input"))
      (node (ref "U18") (pin "2") (pinfunction "D_2") (pintype "unspecified"))
      (node (ref "U2") (pin "1") (pinfunction "VS_1") (pintype "unspecified"))
      (node (ref "U2") (pin "6") (pinfunction "OUT_6") (pintype "unspecified"))
      (node (ref "U4") (pin "4") (pinfunction "EN_4") (pintype "unspecified"))
      (node (ref "U4") (pin "5") (pinfunction "VIN_5") (pintype "unspecified"))
      (node (ref "U6") (pin "3") (pinfunction "VISNS_3") (pintype "unspecified"))
      (node (ref "U7") (pin "2") (pinfunction "D_2") (pintype "unspecified"))
    )
    (net (code "119") (name "VO") (class "Default")
      (node (ref "C38") (pin "1") (pinfunction "1_1") (pintype "input"))
      (node (ref "C40") (pin "2") (pinfunction "2_2") (pintype "input"))
      (node (ref "C41") (pin "2") (pinfunction "2_2") (pintype "input"))
      (node (ref "C42") (pin "2") (pinfunction "2_2") (pintype "input"))
      (node (ref "C49") (pin "2") (pinfunction "2_2") (pintype "input"))
      (node (ref "C50") (pin "2") (pinfunction "2_2") (pintype "input"))
      (node (ref "D26") (pin "1") (pinfunction "K_1") (pintype "unspecified"))
      (node (ref "L6") (pin "1") (pinfunction "1_1") (pintype "input"))
      (node (ref "R35") (pin "2") (pinfunction "2_2") (pintype "input"))
      (node (ref "U9") (pin "2") (pinfunction "D_2") (pintype "unspecified"))
    )
    (net (code "120") (name "VOS") (class "Default")
      (node (ref "R12") (pin "2") (pinfunction "2_2") (pintype "input"))
      (node (ref "R47") (pin "2") (pinfunction "2_2") (pintype "input"))
      (node (ref "U11") (pin "1") (pinfunction "OUT_1_1") (pintype "output"))
      (node (ref "U13") (pin "8") (pinfunction "SENSOR_VN_8") (pintype "unspecified"))
    )
    (net (code "121") (name "VOUT") (class "Default")
      (node (ref "C45") (pin "2") (pinfunction "2_2") (pintype "input"))
      (node (ref "C47") (pin "2") (pinfunction "2_2") (pintype "input"))
      (node (ref "C48") (pin "2") (pinfunction "2_2") (pintype "input"))
      (node (ref "C52") (pin "2") (pinfunction "2_2") (pintype "input"))
      (node (ref "C53") (pin "2") (pinfunction "2_2") (pintype "input"))
      (node (ref "CN2") (pin "4") (pinfunction "4_4") (pintype "unspecified"))
      (node (ref "D11") (pin "1") (pinfunction "K_1") (pintype "unspecified"))
      (node (ref "D12") (pin "2") (pinfunction "A_2") (pintype "unspecified"))
      (node (ref "D7") (pin "2") (pinfunction "2_2") (pintype "unspecified"))
      (node (ref "R15") (pin "1") (pinfunction "1_1") (pintype "input"))
      (node (ref "R36") (pin "2") (pinfunction "2_2") (pintype "unspecified"))
      (node (ref "R37") (pin "2") (pinfunction "2_2") (pintype "unspecified"))
      (node (ref "R38") (pin "2") (pinfunction "2_2") (pintype "unspecified"))
      (node (ref "R40") (pin "1") (pinfunction "1_1") (pintype "input"))
      (node (ref "R50") (pin "2") (pinfunction "2_2") (pintype "input"))
      (node (ref "R53") (pin "2") (pinfunction "2_2") (pintype "input"))
    )
    (net (code "122") (name "VOUTP") (class "Default")
      (node (ref "C39") (pin "1") (pinfunction "1_1") (pintype "input"))
      (node (ref "C43") (pin "2") (pinfunction "2_2") (pintype "input"))
      (node (ref "C44") (pin "2") (pinfunction "2_2") (pintype "input"))
      (node (ref "L6") (pin "2") (pinfunction "2_2") (pintype "input"))
      (node (ref "R16") (pin "1") (pinfunction "1_1") (pintype "input"))
      (node (ref "R36") (pin "1") (pinfunction "1_1") (pintype "unspecified"))
      (node (ref "R37") (pin "1") (pinfunction "1_1") (pintype "unspecified"))
      (node (ref "R38") (pin "1") (pinfunction "1_1") (pintype "unspecified"))
      (node (ref "R39") (pin "1") (pinfunction "1_1") (pintype "input"))
      (node (ref "SCREW4") (pin "1") (pinfunction "1_1") (pintype "input"))
      (node (ref "U6") (pin "12") (pinfunction "VOSNS_12") (pintype "unspecified"))
    )
    (net (code "123") (name "VREF") (class "Default")
      (node (ref "C69") (pin "2") (pinfunction "2_2") (pintype "input"))
      (node (ref "R66") (pin "2") (pinfunction "2_2") (pintype "input"))
      (node (ref "U15") (pin "2") (pinfunction "OUT_2") (pintype "unspecified"))
    )
    (net (code "124") (name "unconnected-(CN1-Pad3)") (class "Default")
      (node (ref "CN1") (pin "3") (pinfunction "3_3") (pintype "unspecified"))
    )
    (net (code "125") (name "unconnected-(CN1-Pad4)") (class "Default")
      (node (ref "CN1") (pin "4") (pinfunction "4_4") (pintype "unspecified"))
    )
    (net (code "126") (name "unconnected-(FPC1-Pad7)") (class "Default")
      (node (ref "FPC1") (pin "7") (pinfunction "7_7") (pintype "unspecified+no_connect"))
    )
    (net (code "127") (name "unconnected-(L5-ANT-Pad1)") (class "Default")
      (node (ref "L5") (pin "1") (pinfunction "ANT_1") (pintype "unspecified"))
    )
    (net (code "128") (name "unconnected-(U3-PG-Pad10)") (class "Default")
      (node (ref "U3") (pin "10") (pinfunction "PG_10") (pintype "unspecified+no_connect"))
    )
    (net (code "129") (name "unconnected-(U10-NC-Pad1)") (class "Default")
      (node (ref "U10") (pin "1") (pinfunction "NC_1") (pintype "unspecified"))
    )
    (net (code "130") (name "unconnected-(U13-CAP1_NC-Pad48)") (class "Default")
      (node (ref "U13") (pin "48") (pinfunction "CAP1_NC_48") (pintype "unspecified+no_connect"))
    )
    (net (code "131") (name "unconnected-(U13-CAP2_NC-Pad47)") (class "Default")
      (node (ref "U13") (pin "47") (pinfunction "CAP2_NC_47") (pintype "unspecified+no_connect"))
    )
    (net (code "132") (name "unconnected-(U13-CLK-Pad31)") (class "Default")
      (node (ref "U13") (pin "31") (pinfunction "CLK_31") (pintype "unspecified+no_connect"))
    )
    (net (code "133") (name "unconnected-(U13-CMD-Pad30)") (class "Default")
      (node (ref "U13") (pin "30") (pinfunction "CMD_30") (pintype "unspecified+no_connect"))
    )
    (net (code "134") (name "unconnected-(U13-IO2-Pad22)") (class "Default")
      (node (ref "U13") (pin "22") (pinfunction "IO2_22") (pintype "unspecified"))
    )
    (net (code "135") (name "unconnected-(U13-IO16-Pad25)") (class "Default")
      (node (ref "U13") (pin "25") (pinfunction "IO16_25") (pintype "unspecified+no_connect"))
    )
    (net (code "136") (name "unconnected-(U13-IO17-Pad27)") (class "Default")
      (node (ref "U13") (pin "27") (pinfunction "IO17_27") (pintype "unspecified+no_connect"))
    )
    (net (code "137") (name "unconnected-(U13-IO27-Pad16)") (class "Default")
      (node (ref "U13") (pin "16") (pinfunction "IO27_16") (pintype "unspecified"))
    )
    (net (code "138") (name "unconnected-(U13-SD0-Pad32)") (class "Default")
      (node (ref "U13") (pin "32") (pinfunction "SD0_32") (pintype "unspecified+no_connect"))
    )
    (net (code "139") (name "unconnected-(U13-SD1-Pad33)") (class "Default")
      (node (ref "U13") (pin "33") (pinfunction "SD1_33") (pintype "unspecified+no_connect"))
    )
    (net (code "140") (name "unconnected-(U13-VDD_SDIO-Pad26)") (class "Default")
      (node (ref "U13") (pin "26") (pinfunction "VDD_SDIO_26") (pintype "unspecified+no_connect"))
    )
    (net (code "141") (name "unconnected-(U13-XTAL_N_NC-Pad44)") (class "Default")
      (node (ref "U13") (pin "44") (pinfunction "XTAL_N_NC_44") (pintype "unspecified+no_connect"))
    )
    (net (code "142") (name "unconnected-(U13-XTAL_P_NC-Pad45)") (class "Default")
      (node (ref "U13") (pin "45") (pinfunction "XTAL_P_NC_45") (pintype "unspecified+no_connect"))
    )
    (net (code "143") (name "unconnected-(U14-CTS#-Pad9)") (class "Default")
      (node (ref "U14") (pin "9") (pinfunction "CTS#_9") (pintype "unspecified+no_connect"))
    )
    (net (code "144") (name "unconnected-(U14-DCD#-Pad12)") (class "Default")
      (node (ref "U14") (pin "12") (pinfunction "DCD#_12") (pintype "unspecified+no_connect"))
    )
    (net (code "145") (name "unconnected-(U14-DSR#-Pad10)") (class "Default")
      (node (ref "U14") (pin "10") (pinfunction "DSR#_10") (pintype "unspecified+no_connect"))
    )
    (net (code "146") (name "unconnected-(U14-NC.-Pad7)") (class "Default")
      (node (ref "U14") (pin "7") (pinfunction "NC._7") (pintype "unspecified+no_connect"))
    )
    (net (code "147") (name "unconnected-(U14-OUT#-Pad8)") (class "Default")
      (node (ref "U14") (pin "8") (pinfunction "OUT#_8") (pintype "unspecified+no_connect"))
    )
    (net (code "148") (name "unconnected-(U14-R232-Pad15)") (class "Default")
      (node (ref "U14") (pin "15") (pinfunction "R232_15") (pintype "unspecified+no_connect"))
    )
    (net (code "149") (name "unconnected-(U14-RI#-Pad11)") (class "Default")
      (node (ref "U14") (pin "11") (pinfunction "RI#_11") (pintype "unspecified+no_connect"))
    )
    (net (code "150") (name "unconnected-(USB1-SUB1-PadA8)") (class "Default")
      (node (ref "USB1") (pin "A8") (pinfunction "SUB1_A8") (pintype "unspecified+no_connect"))
    )
    (net (code "151") (name "unconnected-(USB1-SUB2-PadB8)") (class "Default")
      (node (ref "USB1") (pin "B8") (pinfunction "SUB2_B8") (pintype "unspecified+no_connect"))
    )
  )
)
